# 05_-_Gate_Drivers.net
KiCad netlist of a schematic drawn in Altium Designer
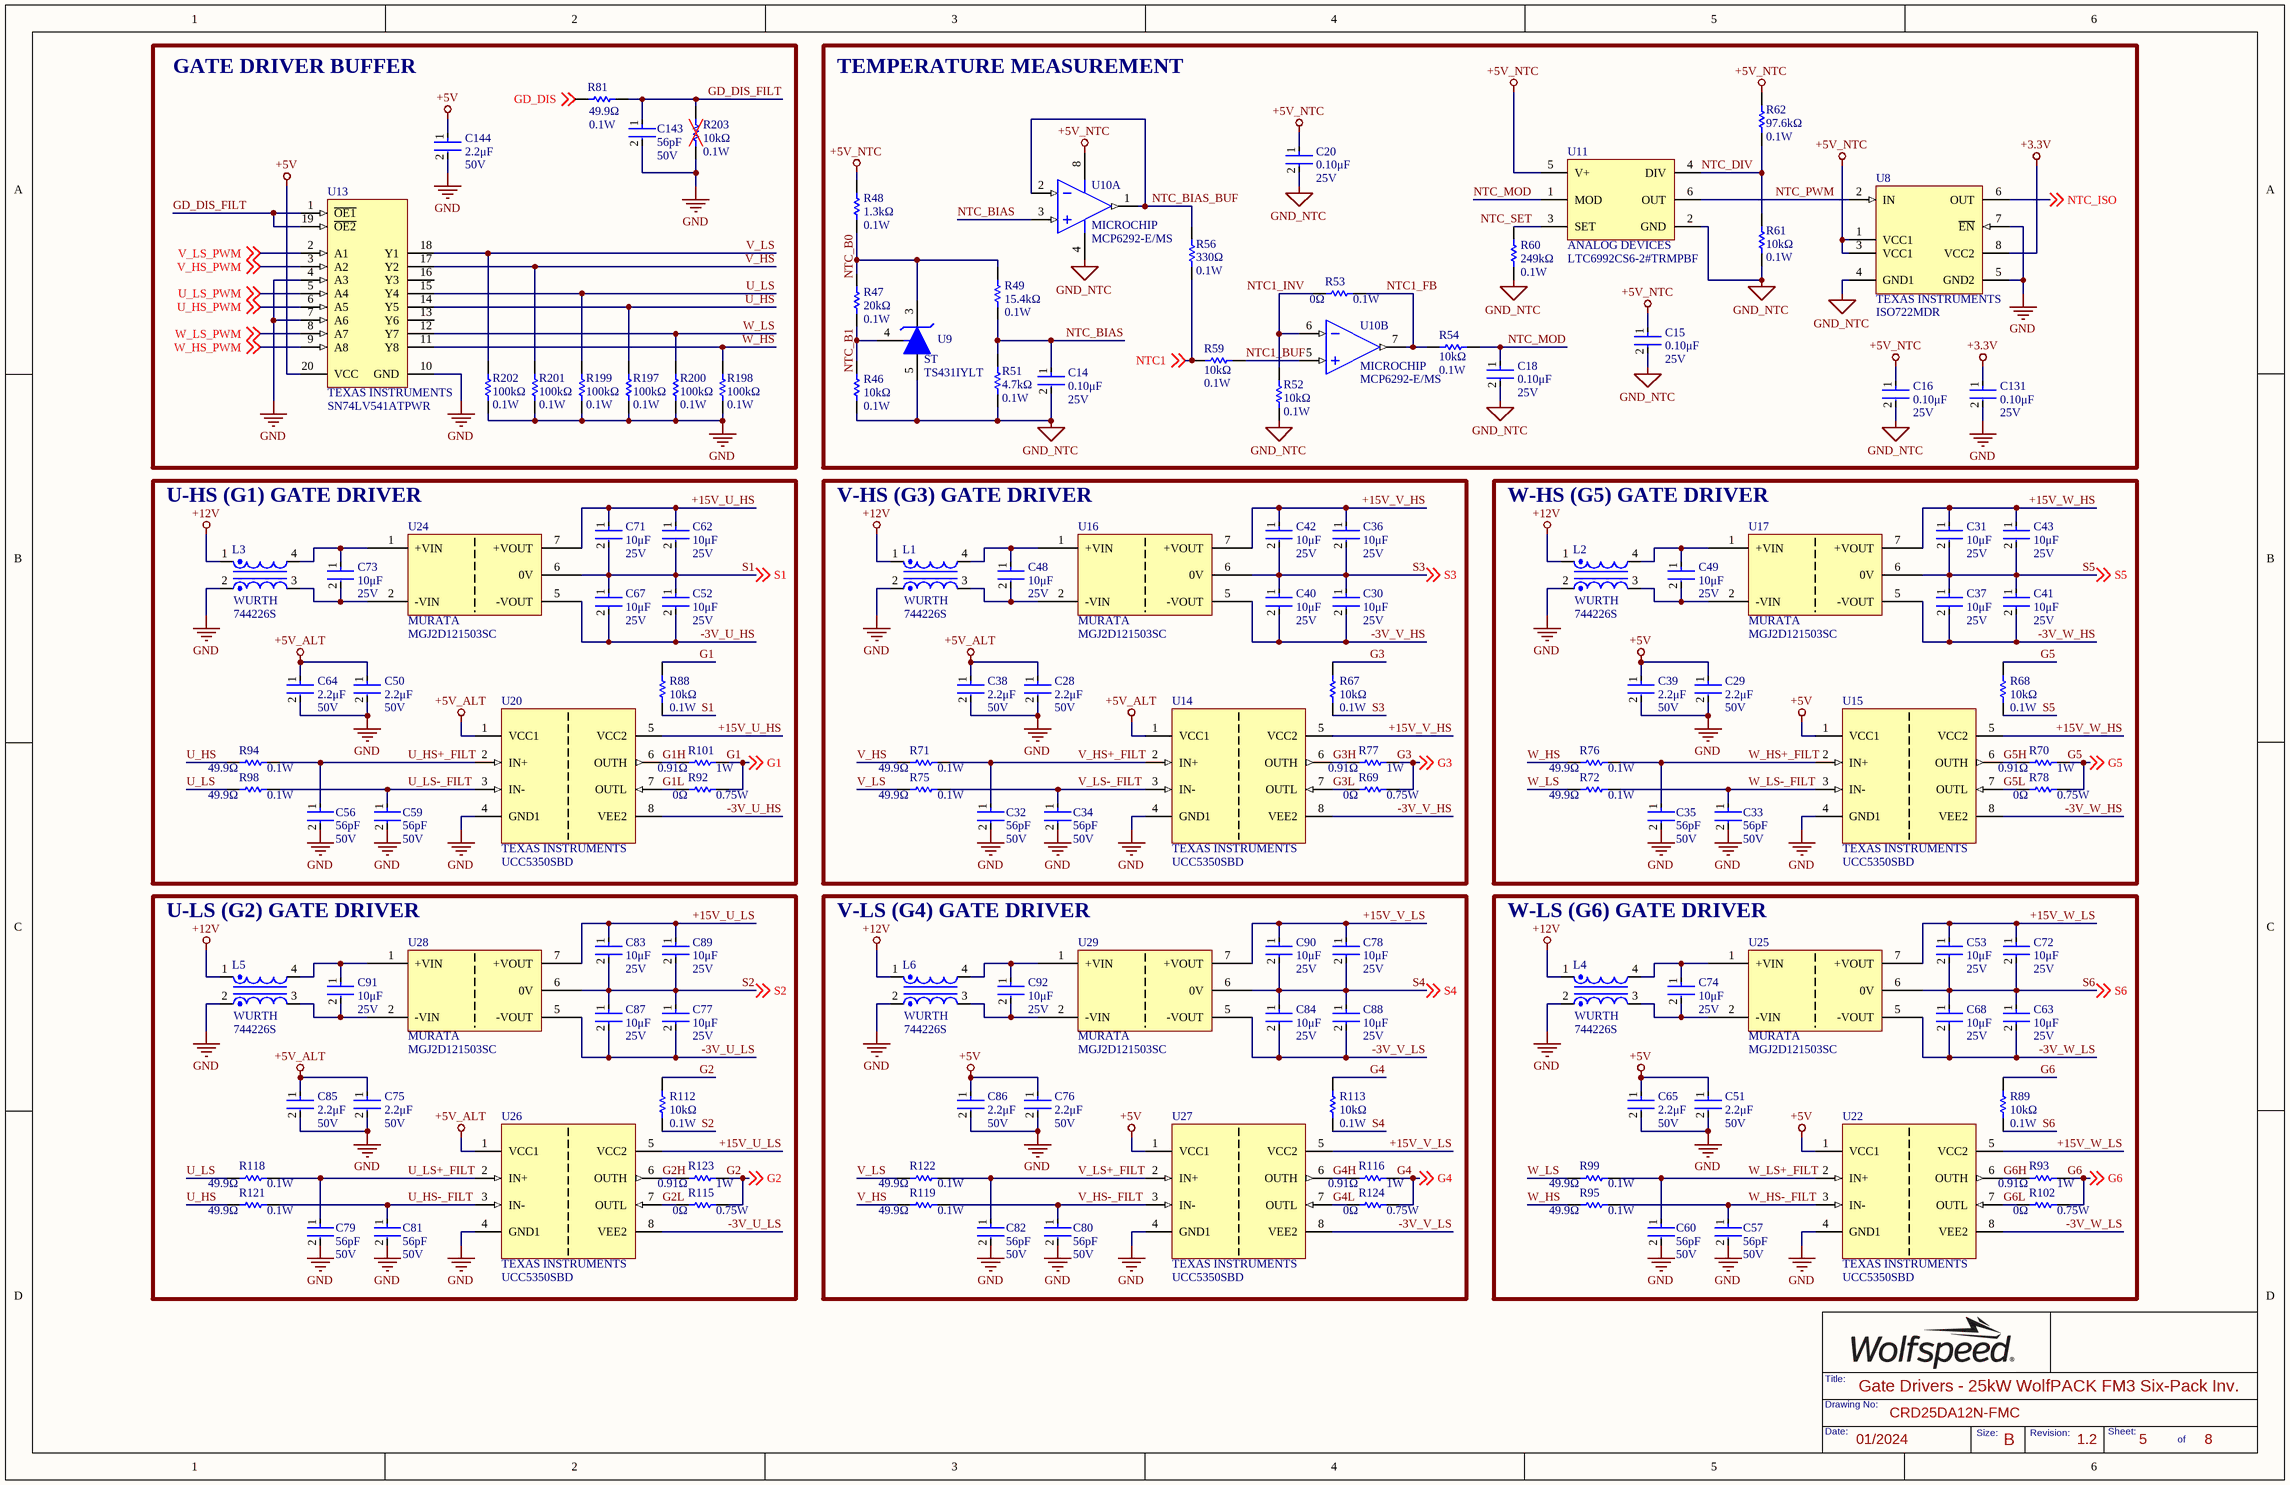
[diagram p0: 05 - Gate Drivers.SchDoc]

(export (version "E")
  (design (tool "Eeschema 10.0.6"))
  (components
    (comp (ref "C14")
      (value "C0603C104K3RACTU")
      (footprint "FP-C0603C-CF-IPC_B")
      (description "CAP CER 0.1UF 25V X7R 0603")
      (fields
        (field (name "VOLTAGE RATING") "25V")
        (field (name "OCTOPART") "https://octopart.com/c0603c104k3ractu-kemet-127541")
        (field (name "MANUFACTURER") "KEMET")
        (field (name "CAPACITANCE") "0.10μF")
      )
      (libsource (lib "Altium Content Vault") (part "b4654b650e69147ec39a6b967a45e02"))
    )
    (comp (ref "C15")
      (value "C0603C104K3RACTU")
      (footprint "FP-C0603C-CF-IPC_B")
      (description "CAP CER 0.1UF 25V X7R 0603")
      (fields
        (field (name "VOLTAGE RATING") "25V")
        (field (name "OCTOPART") "https://octopart.com/c0603c104k3ractu-kemet-127541")
        (field (name "MANUFACTURER") "KEMET")
        (field (name "CAPACITANCE") "0.10μF")
      )
      (libsource (lib "Altium Content Vault") (part "b4654b650e69147ec39a6b967a45e02"))
    )
    (comp (ref "C16")
      (value "C0603C104K3RACTU")
      (footprint "FP-C0603C-CF-IPC_B")
      (description "CAP CER 0.1UF 25V X7R 0603")
      (fields
        (field (name "VOLTAGE RATING") "25V")
        (field (name "OCTOPART") "https://octopart.com/c0603c104k3ractu-kemet-127541")
        (field (name "MANUFACTURER") "KEMET")
        (field (name "CAPACITANCE") "0.10μF")
      )
      (libsource (lib "Altium Content Vault") (part "b4654b650e69147ec39a6b967a45e02"))
    )
    (comp (ref "C18")
      (value "C0603C104K3RACTU")
      (footprint "FP-C0603C-CF-IPC_B")
      (description "CAP CER 0.1UF 25V X7R 0603")
      (fields
        (field (name "VOLTAGE RATING") "25V")
        (field (name "OCTOPART") "https://octopart.com/c0603c104k3ractu-kemet-127541")
        (field (name "MANUFACTURER") "KEMET")
        (field (name "CAPACITANCE") "0.10μF")
      )
      (libsource (lib "Altium Content Vault") (part "b4654b650e69147ec39a6b967a45e02"))
    )
    (comp (ref "C20")
      (value "C0603C104K3RACTU")
      (footprint "FP-C0603C-CF-IPC_B")
      (description "CAP CER 0.1UF 25V X7R 0603")
      (fields
        (field (name "VOLTAGE RATING") "25V")
        (field (name "OCTOPART") "https://octopart.com/c0603c104k3ractu-kemet-127541")
        (field (name "MANUFACTURER") "KEMET")
        (field (name "CAPACITANCE") "0.10μF")
      )
      (libsource (lib "Altium Content Vault") (part "b4654b650e69147ec39a6b967a45e02"))
    )
    (comp (ref "C28")
      (value "GRT188R61H225ME13D")
      (footprint "FP-C0603C-CF-IPC_B")
      (description "CAP CER 2.2UF 50V X5R 0603")
      (fields
        (field (name "MANUFACTURER") "MURATA")
        (field (name "TOLERANCE") "20%")
        (field (name "VOLTAGE RATING") "50V")
        (field (name "CAPACITANCE") "2.2μF")
      )
      (libsource (lib "Inverter_25kW") (part "GRT188R61H225ME13D"))
    )
    (comp (ref "C29")
      (value "GRT188R61H225ME13D")
      (footprint "FP-C0603C-CF-IPC_B")
      (description "CAP CER 2.2UF 50V X5R 0603")
      (fields
        (field (name "MANUFACTURER") "MURATA")
        (field (name "TOLERANCE") "20%")
        (field (name "VOLTAGE RATING") "50V")
        (field (name "CAPACITANCE") "2.2μF")
      )
      (libsource (lib "Inverter_25kW") (part "GRT188R61H225ME13D"))
    )
    (comp (ref "C30")
      (value "CL31B106KAHSFNE")
      (footprint "FP-CL31-IPC_B")
      (description "CAP CER 10UF 25V X7R 1206")
      (fields
        (field (name "VOLTAGE RATING") "25V")
        (field (name "TOLERANCE") "10%")
        (field (name "CAPACITANCE") "10μF")
        (field (name "MANUFACTURER") "SAMSUNG")
      )
      (libsource (lib "Altium Content Vault") (part "b4654b650e69147ec39a6b967a45e02"))
    )
    (comp (ref "C31")
      (value "CL31B106KAHSFNE")
      (footprint "FP-CL31-IPC_B")
      (description "CAP CER 10UF 25V X7R 1206")
      (fields
        (field (name "VOLTAGE RATING") "25V")
        (field (name "TOLERANCE") "10%")
        (field (name "CAPACITANCE") "10μF")
        (field (name "MANUFACTURER") "SAMSUNG")
      )
      (libsource (lib "Altium Content Vault") (part "b4654b650e69147ec39a6b967a45e02"))
    )
    (comp (ref "C32")
      (value "CL10C560JB8NNNC")
      (footprint "FP-C0603C-CF-IPC_B")
      (description "CAP CER 56PF 50V C0G/NP0 0603")
      (fields
        (field (name "MANUFACTURER") "SAMSUNG")
        (field (name "TOLERANCE") "5%")
        (field (name "CAPACITANCE") "56pF")
        (field (name "VOLTAGE RATING") "50V")
      )
      (libsource (lib "Inverter_25kW") (part "CL10C560JB8NNNC"))
    )
    (comp (ref "C33")
      (value "CL10C560JB8NNNC")
      (footprint "FP-C0603C-CF-IPC_B")
      (description "CAP CER 56PF 50V C0G/NP0 0603")
      (fields
        (field (name "MANUFACTURER") "SAMSUNG")
        (field (name "TOLERANCE") "5%")
        (field (name "CAPACITANCE") "56pF")
        (field (name "VOLTAGE RATING") "50V")
      )
      (libsource (lib "Inverter_25kW") (part "CL10C560JB8NNNC"))
    )
    (comp (ref "C34")
      (value "CL10C560JB8NNNC")
      (footprint "FP-C0603C-CF-IPC_B")
      (description "CAP CER 56PF 50V C0G/NP0 0603")
      (fields
        (field (name "MANUFACTURER") "SAMSUNG")
        (field (name "TOLERANCE") "5%")
        (field (name "CAPACITANCE") "56pF")
        (field (name "VOLTAGE RATING") "50V")
      )
      (libsource (lib "Inverter_25kW") (part "CL10C560JB8NNNC"))
    )
    (comp (ref "C35")
      (value "CL10C560JB8NNNC")
      (footprint "FP-C0603C-CF-IPC_B")
      (description "CAP CER 56PF 50V C0G/NP0 0603")
      (fields
        (field (name "MANUFACTURER") "SAMSUNG")
        (field (name "TOLERANCE") "5%")
        (field (name "CAPACITANCE") "56pF")
        (field (name "VOLTAGE RATING") "50V")
      )
      (libsource (lib "Inverter_25kW") (part "CL10C560JB8NNNC"))
    )
    (comp (ref "C36")
      (value "CL31B106KAHSFNE")
      (footprint "FP-CL31-IPC_B")
      (description "CAP CER 10UF 25V X7R 1206")
      (fields
        (field (name "VOLTAGE RATING") "25V")
        (field (name "TOLERANCE") "10%")
        (field (name "CAPACITANCE") "10μF")
        (field (name "MANUFACTURER") "SAMSUNG")
      )
      (libsource (lib "Altium Content Vault") (part "b4654b650e69147ec39a6b967a45e02"))
    )
    (comp (ref "C37")
      (value "CL31B106KAHSFNE")
      (footprint "FP-CL31-IPC_B")
      (description "CAP CER 10UF 25V X7R 1206")
      (fields
        (field (name "VOLTAGE RATING") "25V")
        (field (name "TOLERANCE") "10%")
        (field (name "CAPACITANCE") "10μF")
        (field (name "MANUFACTURER") "SAMSUNG")
      )
      (libsource (lib "Altium Content Vault") (part "b4654b650e69147ec39a6b967a45e02"))
    )
    (comp (ref "C38")
      (value "GRT188R61H225ME13D")
      (footprint "FP-C0603C-CF-IPC_B")
      (description "CAP CER 2.2UF 50V X5R 0603")
      (fields
        (field (name "MANUFACTURER") "MURATA")
        (field (name "TOLERANCE") "20%")
        (field (name "VOLTAGE RATING") "50V")
        (field (name "CAPACITANCE") "2.2μF")
      )
      (libsource (lib "Inverter_25kW") (part "GRT188R61H225ME13D"))
    )
    (comp (ref "C39")
      (value "GRT188R61H225ME13D")
      (footprint "FP-C0603C-CF-IPC_B")
      (description "CAP CER 2.2UF 50V X5R 0603")
      (fields
        (field (name "MANUFACTURER") "MURATA")
        (field (name "TOLERANCE") "20%")
        (field (name "VOLTAGE RATING") "50V")
        (field (name "CAPACITANCE") "2.2μF")
      )
      (libsource (lib "Inverter_25kW") (part "GRT188R61H225ME13D"))
    )
    (comp (ref "C40")
      (value "CL31B106KAHSFNE")
      (footprint "FP-CL31-IPC_B")
      (description "CAP CER 10UF 25V X7R 1206")
      (fields
        (field (name "VOLTAGE RATING") "25V")
        (field (name "TOLERANCE") "10%")
        (field (name "CAPACITANCE") "10μF")
        (field (name "MANUFACTURER") "SAMSUNG")
      )
      (libsource (lib "Altium Content Vault") (part "b4654b650e69147ec39a6b967a45e02"))
    )
    (comp (ref "C41")
      (value "CL31B106KAHSFNE")
      (footprint "FP-CL31-IPC_B")
      (description "CAP CER 10UF 25V X7R 1206")
      (fields
        (field (name "VOLTAGE RATING") "25V")
        (field (name "TOLERANCE") "10%")
        (field (name "CAPACITANCE") "10μF")
        (field (name "MANUFACTURER") "SAMSUNG")
      )
      (libsource (lib "Altium Content Vault") (part "b4654b650e69147ec39a6b967a45e02"))
    )
    (comp (ref "C42")
      (value "CL31B106KAHSFNE")
      (footprint "FP-CL31-IPC_B")
      (description "CAP CER 10UF 25V X7R 1206")
      (fields
        (field (name "VOLTAGE RATING") "25V")
        (field (name "TOLERANCE") "10%")
        (field (name "CAPACITANCE") "10μF")
        (field (name "MANUFACTURER") "SAMSUNG")
      )
      (libsource (lib "Altium Content Vault") (part "b4654b650e69147ec39a6b967a45e02"))
    )
    (comp (ref "C43")
      (value "CL31B106KAHSFNE")
      (footprint "FP-CL31-IPC_B")
      (description "CAP CER 10UF 25V X7R 1206")
      (fields
        (field (name "VOLTAGE RATING") "25V")
        (field (name "TOLERANCE") "10%")
        (field (name "CAPACITANCE") "10μF")
        (field (name "MANUFACTURER") "SAMSUNG")
      )
      (libsource (lib "Altium Content Vault") (part "b4654b650e69147ec39a6b967a45e02"))
    )
    (comp (ref "C48")
      (value "CL31B106KAHSFNE")
      (footprint "FP-CL31-IPC_B")
      (description "CAP CER 10UF 25V X7R 1206")
      (fields
        (field (name "VOLTAGE RATING") "25V")
        (field (name "TOLERANCE") "10%")
        (field (name "CAPACITANCE") "10μF")
        (field (name "MANUFACTURER") "SAMSUNG")
      )
      (libsource (lib "Altium Content Vault") (part "b4654b650e69147ec39a6b967a45e02"))
    )
    (comp (ref "C49")
      (value "CL31B106KAHSFNE")
      (footprint "FP-CL31-IPC_B")
      (description "CAP CER 10UF 25V X7R 1206")
      (fields
        (field (name "VOLTAGE RATING") "25V")
        (field (name "TOLERANCE") "10%")
        (field (name "CAPACITANCE") "10μF")
        (field (name "MANUFACTURER") "SAMSUNG")
      )
      (libsource (lib "Altium Content Vault") (part "b4654b650e69147ec39a6b967a45e02"))
    )
    (comp (ref "C50")
      (value "GRT188R61H225ME13D")
      (footprint "FP-C0603C-CF-IPC_B")
      (description "CAP CER 2.2UF 50V X5R 0603")
      (fields
        (field (name "MANUFACTURER") "MURATA")
        (field (name "TOLERANCE") "20%")
        (field (name "VOLTAGE RATING") "50V")
        (field (name "CAPACITANCE") "2.2μF")
      )
      (libsource (lib "Inverter_25kW") (part "GRT188R61H225ME13D"))
    )
    (comp (ref "C51")
      (value "GRT188R61H225ME13D")
      (footprint "FP-C0603C-CF-IPC_B")
      (description "CAP CER 2.2UF 50V X5R 0603")
      (fields
        (field (name "MANUFACTURER") "MURATA")
        (field (name "TOLERANCE") "20%")
        (field (name "VOLTAGE RATING") "50V")
        (field (name "CAPACITANCE") "2.2μF")
      )
      (libsource (lib "Inverter_25kW") (part "GRT188R61H225ME13D"))
    )
    (comp (ref "C52")
      (value "CL31B106KAHSFNE")
      (footprint "FP-CL31-IPC_B")
      (description "CAP CER 10UF 25V X7R 1206")
      (fields
        (field (name "VOLTAGE RATING") "25V")
        (field (name "TOLERANCE") "10%")
        (field (name "CAPACITANCE") "10μF")
        (field (name "MANUFACTURER") "SAMSUNG")
      )
      (libsource (lib "Altium Content Vault") (part "b4654b650e69147ec39a6b967a45e02"))
    )
    (comp (ref "C53")
      (value "CL31B106KAHSFNE")
      (footprint "FP-CL31-IPC_B")
      (description "CAP CER 10UF 25V X7R 1206")
      (fields
        (field (name "VOLTAGE RATING") "25V")
        (field (name "TOLERANCE") "10%")
        (field (name "CAPACITANCE") "10μF")
        (field (name "MANUFACTURER") "SAMSUNG")
      )
      (libsource (lib "Altium Content Vault") (part "b4654b650e69147ec39a6b967a45e02"))
    )
    (comp (ref "C56")
      (value "CL10C560JB8NNNC")
      (footprint "FP-C0603C-CF-IPC_B")
      (description "CAP CER 56PF 50V C0G/NP0 0603")
      (fields
        (field (name "MANUFACTURER") "SAMSUNG")
        (field (name "TOLERANCE") "5%")
        (field (name "CAPACITANCE") "56pF")
        (field (name "VOLTAGE RATING") "50V")
      )
      (libsource (lib "Inverter_25kW") (part "CL10C560JB8NNNC"))
    )
    (comp (ref "C57")
      (value "CL10C560JB8NNNC")
      (footprint "FP-C0603C-CF-IPC_B")
      (description "CAP CER 56PF 50V C0G/NP0 0603")
      (fields
        (field (name "MANUFACTURER") "SAMSUNG")
        (field (name "TOLERANCE") "5%")
        (field (name "CAPACITANCE") "56pF")
        (field (name "VOLTAGE RATING") "50V")
      )
      (libsource (lib "Inverter_25kW") (part "CL10C560JB8NNNC"))
    )
    (comp (ref "C59")
      (value "CL10C560JB8NNNC")
      (footprint "FP-C0603C-CF-IPC_B")
      (description "CAP CER 56PF 50V C0G/NP0 0603")
      (fields
        (field (name "MANUFACTURER") "SAMSUNG")
        (field (name "TOLERANCE") "5%")
        (field (name "CAPACITANCE") "56pF")
        (field (name "VOLTAGE RATING") "50V")
      )
      (libsource (lib "Inverter_25kW") (part "CL10C560JB8NNNC"))
    )
    (comp (ref "C60")
      (value "CL10C560JB8NNNC")
      (footprint "FP-C0603C-CF-IPC_B")
      (description "CAP CER 56PF 50V C0G/NP0 0603")
      (fields
        (field (name "MANUFACTURER") "SAMSUNG")
        (field (name "TOLERANCE") "5%")
        (field (name "CAPACITANCE") "56pF")
        (field (name "VOLTAGE RATING") "50V")
      )
      (libsource (lib "Inverter_25kW") (part "CL10C560JB8NNNC"))
    )
    (comp (ref "C62")
      (value "CL31B106KAHSFNE")
      (footprint "FP-CL31-IPC_B")
      (description "CAP CER 10UF 25V X7R 1206")
      (fields
        (field (name "VOLTAGE RATING") "25V")
        (field (name "TOLERANCE") "10%")
        (field (name "CAPACITANCE") "10μF")
        (field (name "MANUFACTURER") "SAMSUNG")
      )
      (libsource (lib "Altium Content Vault") (part "b4654b650e69147ec39a6b967a45e02"))
    )
    (comp (ref "C63")
      (value "CL31B106KAHSFNE")
      (footprint "FP-CL31-IPC_B")
      (description "CAP CER 10UF 25V X7R 1206")
      (fields
        (field (name "VOLTAGE RATING") "25V")
        (field (name "TOLERANCE") "10%")
        (field (name "CAPACITANCE") "10μF")
        (field (name "MANUFACTURER") "SAMSUNG")
      )
      (libsource (lib "Altium Content Vault") (part "b4654b650e69147ec39a6b967a45e02"))
    )
    (comp (ref "C64")
      (value "GRT188R61H225ME13D")
      (footprint "FP-C0603C-CF-IPC_B")
      (description "CAP CER 2.2UF 50V X5R 0603")
      (fields
        (field (name "MANUFACTURER") "MURATA")
        (field (name "TOLERANCE") "20%")
        (field (name "VOLTAGE RATING") "50V")
        (field (name "CAPACITANCE") "2.2μF")
      )
      (libsource (lib "Inverter_25kW") (part "GRT188R61H225ME13D"))
    )
    (comp (ref "C65")
      (value "GRT188R61H225ME13D")
      (footprint "FP-C0603C-CF-IPC_B")
      (description "CAP CER 2.2UF 50V X5R 0603")
      (fields
        (field (name "MANUFACTURER") "MURATA")
        (field (name "TOLERANCE") "20%")
        (field (name "VOLTAGE RATING") "50V")
        (field (name "CAPACITANCE") "2.2μF")
      )
      (libsource (lib "Inverter_25kW") (part "GRT188R61H225ME13D"))
    )
    (comp (ref "C67")
      (value "CL31B106KAHSFNE")
      (footprint "FP-CL31-IPC_B")
      (description "CAP CER 10UF 25V X7R 1206")
      (fields
        (field (name "VOLTAGE RATING") "25V")
        (field (name "TOLERANCE") "10%")
        (field (name "CAPACITANCE") "10μF")
        (field (name "MANUFACTURER") "SAMSUNG")
      )
      (libsource (lib "Altium Content Vault") (part "b4654b650e69147ec39a6b967a45e02"))
    )
    (comp (ref "C68")
      (value "CL31B106KAHSFNE")
      (footprint "FP-CL31-IPC_B")
      (description "CAP CER 10UF 25V X7R 1206")
      (fields
        (field (name "VOLTAGE RATING") "25V")
        (field (name "TOLERANCE") "10%")
        (field (name "CAPACITANCE") "10μF")
        (field (name "MANUFACTURER") "SAMSUNG")
      )
      (libsource (lib "Altium Content Vault") (part "b4654b650e69147ec39a6b967a45e02"))
    )
    (comp (ref "C71")
      (value "CL31B106KAHSFNE")
      (footprint "FP-CL31-IPC_B")
      (description "CAP CER 10UF 25V X7R 1206")
      (fields
        (field (name "VOLTAGE RATING") "25V")
        (field (name "TOLERANCE") "10%")
        (field (name "CAPACITANCE") "10μF")
        (field (name "MANUFACTURER") "SAMSUNG")
      )
      (libsource (lib "Altium Content Vault") (part "b4654b650e69147ec39a6b967a45e02"))
    )
    (comp (ref "C72")
      (value "CL31B106KAHSFNE")
      (footprint "FP-CL31-IPC_B")
      (description "CAP CER 10UF 25V X7R 1206")
      (fields
        (field (name "VOLTAGE RATING") "25V")
        (field (name "TOLERANCE") "10%")
        (field (name "CAPACITANCE") "10μF")
        (field (name "MANUFACTURER") "SAMSUNG")
      )
      (libsource (lib "Altium Content Vault") (part "b4654b650e69147ec39a6b967a45e02"))
    )
    (comp (ref "C73")
      (value "CL31B106KAHSFNE")
      (footprint "FP-CL31-IPC_B")
      (description "CAP CER 10UF 25V X7R 1206")
      (fields
        (field (name "VOLTAGE RATING") "25V")
        (field (name "TOLERANCE") "10%")
        (field (name "CAPACITANCE") "10μF")
        (field (name "MANUFACTURER") "SAMSUNG")
      )
      (libsource (lib "Altium Content Vault") (part "b4654b650e69147ec39a6b967a45e02"))
    )
    (comp (ref "C74")
      (value "CL31B106KAHSFNE")
      (footprint "FP-CL31-IPC_B")
      (description "CAP CER 10UF 25V X7R 1206")
      (fields
        (field (name "VOLTAGE RATING") "25V")
        (field (name "TOLERANCE") "10%")
        (field (name "CAPACITANCE") "10μF")
        (field (name "MANUFACTURER") "SAMSUNG")
      )
      (libsource (lib "Altium Content Vault") (part "b4654b650e69147ec39a6b967a45e02"))
    )
    (comp (ref "C75")
      (value "GRT188R61H225ME13D")
      (footprint "FP-C0603C-CF-IPC_B")
      (description "CAP CER 2.2UF 50V X5R 0603")
      (fields
        (field (name "MANUFACTURER") "MURATA")
        (field (name "TOLERANCE") "20%")
        (field (name "VOLTAGE RATING") "50V")
        (field (name "CAPACITANCE") "2.2μF")
      )
      (libsource (lib "Inverter_25kW") (part "GRT188R61H225ME13D"))
    )
    (comp (ref "C76")
      (value "GRT188R61H225ME13D")
      (footprint "FP-C0603C-CF-IPC_B")
      (description "CAP CER 2.2UF 50V X5R 0603")
      (fields
        (field (name "MANUFACTURER") "MURATA")
        (field (name "TOLERANCE") "20%")
        (field (name "VOLTAGE RATING") "50V")
        (field (name "CAPACITANCE") "2.2μF")
      )
      (libsource (lib "Inverter_25kW") (part "GRT188R61H225ME13D"))
    )
    (comp (ref "C77")
      (value "CL31B106KAHSFNE")
      (footprint "FP-CL31-IPC_B")
      (description "CAP CER 10UF 25V X7R 1206")
      (fields
        (field (name "VOLTAGE RATING") "25V")
        (field (name "TOLERANCE") "10%")
        (field (name "CAPACITANCE") "10μF")
        (field (name "MANUFACTURER") "SAMSUNG")
      )
      (libsource (lib "Altium Content Vault") (part "b4654b650e69147ec39a6b967a45e02"))
    )
    (comp (ref "C78")
      (value "CL31B106KAHSFNE")
      (footprint "FP-CL31-IPC_B")
      (description "CAP CER 10UF 25V X7R 1206")
      (fields
        (field (name "VOLTAGE RATING") "25V")
        (field (name "TOLERANCE") "10%")
        (field (name "CAPACITANCE") "10μF")
        (field (name "MANUFACTURER") "SAMSUNG")
      )
      (libsource (lib "Altium Content Vault") (part "b4654b650e69147ec39a6b967a45e02"))
    )
    (comp (ref "C79")
      (value "CL10C560JB8NNNC")
      (footprint "FP-C0603C-CF-IPC_B")
      (description "CAP CER 56PF 50V C0G/NP0 0603")
      (fields
        (field (name "MANUFACTURER") "SAMSUNG")
        (field (name "TOLERANCE") "5%")
        (field (name "CAPACITANCE") "56pF")
        (field (name "VOLTAGE RATING") "50V")
      )
      (libsource (lib "Inverter_25kW") (part "CL10C560JB8NNNC"))
    )
    (comp (ref "C80")
      (value "CL10C560JB8NNNC")
      (footprint "FP-C0603C-CF-IPC_B")
      (description "CAP CER 56PF 50V C0G/NP0 0603")
      (fields
        (field (name "MANUFACTURER") "SAMSUNG")
        (field (name "TOLERANCE") "5%")
        (field (name "CAPACITANCE") "56pF")
        (field (name "VOLTAGE RATING") "50V")
      )
      (libsource (lib "Inverter_25kW") (part "CL10C560JB8NNNC"))
    )
    (comp (ref "C81")
      (value "CL10C560JB8NNNC")
      (footprint "FP-C0603C-CF-IPC_B")
      (description "CAP CER 56PF 50V C0G/NP0 0603")
      (fields
        (field (name "MANUFACTURER") "SAMSUNG")
        (field (name "TOLERANCE") "5%")
        (field (name "CAPACITANCE") "56pF")
        (field (name "VOLTAGE RATING") "50V")
      )
      (libsource (lib "Inverter_25kW") (part "CL10C560JB8NNNC"))
    )
    (comp (ref "C82")
      (value "CL10C560JB8NNNC")
      (footprint "FP-C0603C-CF-IPC_B")
      (description "CAP CER 56PF 50V C0G/NP0 0603")
      (fields
        (field (name "MANUFACTURER") "SAMSUNG")
        (field (name "TOLERANCE") "5%")
        (field (name "CAPACITANCE") "56pF")
        (field (name "VOLTAGE RATING") "50V")
      )
      (libsource (lib "Inverter_25kW") (part "CL10C560JB8NNNC"))
    )
    (comp (ref "C83")
      (value "CL31B106KAHSFNE")
      (footprint "FP-CL31-IPC_B")
      (description "CAP CER 10UF 25V X7R 1206")
      (fields
        (field (name "VOLTAGE RATING") "25V")
        (field (name "TOLERANCE") "10%")
        (field (name "CAPACITANCE") "10μF")
        (field (name "MANUFACTURER") "SAMSUNG")
      )
      (libsource (lib "Altium Content Vault") (part "b4654b650e69147ec39a6b967a45e02"))
    )
    (comp (ref "C84")
      (value "CL31B106KAHSFNE")
      (footprint "FP-CL31-IPC_B")
      (description "CAP CER 10UF 25V X7R 1206")
      (fields
        (field (name "VOLTAGE RATING") "25V")
        (field (name "TOLERANCE") "10%")
        (field (name "CAPACITANCE") "10μF")
        (field (name "MANUFACTURER") "SAMSUNG")
      )
      (libsource (lib "Altium Content Vault") (part "b4654b650e69147ec39a6b967a45e02"))
    )
    (comp (ref "C85")
      (value "GRT188R61H225ME13D")
      (footprint "FP-C0603C-CF-IPC_B")
      (description "CAP CER 2.2UF 50V X5R 0603")
      (fields
        (field (name "MANUFACTURER") "MURATA")
        (field (name "TOLERANCE") "20%")
        (field (name "VOLTAGE RATING") "50V")
        (field (name "CAPACITANCE") "2.2μF")
      )
      (libsource (lib "Inverter_25kW") (part "GRT188R61H225ME13D"))
    )
    (comp (ref "C86")
      (value "GRT188R61H225ME13D")
      (footprint "FP-C0603C-CF-IPC_B")
      (description "CAP CER 2.2UF 50V X5R 0603")
      (fields
        (field (name "MANUFACTURER") "MURATA")
        (field (name "TOLERANCE") "20%")
        (field (name "VOLTAGE RATING") "50V")
        (field (name "CAPACITANCE") "2.2μF")
      )
      (libsource (lib "Inverter_25kW") (part "GRT188R61H225ME13D"))
    )
    (comp (ref "C87")
      (value "CL31B106KAHSFNE")
      (footprint "FP-CL31-IPC_B")
      (description "CAP CER 10UF 25V X7R 1206")
      (fields
        (field (name "VOLTAGE RATING") "25V")
        (field (name "TOLERANCE") "10%")
        (field (name "CAPACITANCE") "10μF")
        (field (name "MANUFACTURER") "SAMSUNG")
      )
      (libsource (lib "Altium Content Vault") (part "b4654b650e69147ec39a6b967a45e02"))
    )
    (comp (ref "C88")
      (value "CL31B106KAHSFNE")
      (footprint "FP-CL31-IPC_B")
      (description "CAP CER 10UF 25V X7R 1206")
      (fields
        (field (name "VOLTAGE RATING") "25V")
        (field (name "TOLERANCE") "10%")
        (field (name "CAPACITANCE") "10μF")
        (field (name "MANUFACTURER") "SAMSUNG")
      )
      (libsource (lib "Altium Content Vault") (part "b4654b650e69147ec39a6b967a45e02"))
    )
    (comp (ref "C89")
      (value "CL31B106KAHSFNE")
      (footprint "FP-CL31-IPC_B")
      (description "CAP CER 10UF 25V X7R 1206")
      (fields
        (field (name "VOLTAGE RATING") "25V")
        (field (name "TOLERANCE") "10%")
        (field (name "CAPACITANCE") "10μF")
        (field (name "MANUFACTURER") "SAMSUNG")
      )
      (libsource (lib "Altium Content Vault") (part "b4654b650e69147ec39a6b967a45e02"))
    )
    (comp (ref "C90")
      (value "CL31B106KAHSFNE")
      (footprint "FP-CL31-IPC_B")
      (description "CAP CER 10UF 25V X7R 1206")
      (fields
        (field (name "VOLTAGE RATING") "25V")
        (field (name "TOLERANCE") "10%")
        (field (name "CAPACITANCE") "10μF")
        (field (name "MANUFACTURER") "SAMSUNG")
      )
      (libsource (lib "Altium Content Vault") (part "b4654b650e69147ec39a6b967a45e02"))
    )
    (comp (ref "C91")
      (value "CL31B106KAHSFNE")
      (footprint "FP-CL31-IPC_B")
      (description "CAP CER 10UF 25V X7R 1206")
      (fields
        (field (name "VOLTAGE RATING") "25V")
        (field (name "TOLERANCE") "10%")
        (field (name "CAPACITANCE") "10μF")
        (field (name "MANUFACTURER") "SAMSUNG")
      )
      (libsource (lib "Altium Content Vault") (part "b4654b650e69147ec39a6b967a45e02"))
    )
    (comp (ref "C92")
      (value "CL31B106KAHSFNE")
      (footprint "FP-CL31-IPC_B")
      (description "CAP CER 10UF 25V X7R 1206")
      (fields
        (field (name "VOLTAGE RATING") "25V")
        (field (name "TOLERANCE") "10%")
        (field (name "CAPACITANCE") "10μF")
        (field (name "MANUFACTURER") "SAMSUNG")
      )
      (libsource (lib "Altium Content Vault") (part "b4654b650e69147ec39a6b967a45e02"))
    )
    (comp (ref "C131")
      (value "C0603C104K3RACTU")
      (footprint "FP-C0603C-CF-IPC_B")
      (description "CAP CER 0.1UF 25V X7R 0603")
      (fields
        (field (name "VOLTAGE RATING") "25V")
        (field (name "OCTOPART") "https://octopart.com/c0603c104k3ractu-kemet-127541")
        (field (name "MANUFACTURER") "KEMET")
        (field (name "CAPACITANCE") "0.10μF")
      )
      (libsource (lib "Altium Content Vault") (part "b4654b650e69147ec39a6b967a45e02"))
    )
    (comp (ref "C143")
      (value "CL10C560JB8NNNC")
      (footprint "FP-C0603C-CF-IPC_B")
      (description "CAP CER 56PF 50V C0G/NP0 0603")
      (fields
        (field (name "MANUFACTURER") "SAMSUNG")
        (field (name "TOLERANCE") "5%")
        (field (name "CAPACITANCE") "56pF")
        (field (name "VOLTAGE RATING") "50V")
      )
      (libsource (lib "Inverter_25kW") (part "CL10C560JB8NNNC"))
    )
    (comp (ref "C144")
      (value "GRT188R61H225ME13D")
      (footprint "FP-C0603C-CF-IPC_B")
      (description "CAP CER 2.2UF 50V X5R 0603")
      (fields
        (field (name "MANUFACTURER") "MURATA")
        (field (name "TOLERANCE") "20%")
        (field (name "VOLTAGE RATING") "50V")
        (field (name "CAPACITANCE") "2.2μF")
      )
      (libsource (lib "Inverter_25kW") (part "GRT188R61H225ME13D"))
    )
    (comp (ref "L1")
      (value "744226S")
      (footprint "Inverter_25kW:WE-SL2")
      (description "CMC 10UH 1.6A 2LN 920 OHM SMD")
      (fields
        (field (name "MANUFACTURER") "WURTH ELECTRONIK")
        (field (name "TOLERANCE") "30%")
        (field (name "MANUFACTURER PRINT") "WURTH")
      )
      (libsource (lib "Inverter_25kW") (part "744226S"))
    )
    (comp (ref "L2")
      (value "744226S")
      (footprint "Inverter_25kW:WE-SL2")
      (description "CMC 10UH 1.6A 2LN 920 OHM SMD")
      (fields
        (field (name "MANUFACTURER") "WURTH ELECTRONIK")
        (field (name "TOLERANCE") "30%")
        (field (name "MANUFACTURER PRINT") "WURTH")
      )
      (libsource (lib "Inverter_25kW") (part "744226S"))
    )
    (comp (ref "L3")
      (value "744226S")
      (footprint "Inverter_25kW:WE-SL2")
      (description "CMC 10UH 1.6A 2LN 920 OHM SMD")
      (fields
        (field (name "MANUFACTURER") "WURTH ELECTRONIK")
        (field (name "TOLERANCE") "30%")
        (field (name "MANUFACTURER PRINT") "WURTH")
      )
      (libsource (lib "Inverter_25kW") (part "744226S"))
    )
    (comp (ref "L4")
      (value "744226S")
      (footprint "Inverter_25kW:WE-SL2")
      (description "CMC 10UH 1.6A 2LN 920 OHM SMD")
      (fields
        (field (name "MANUFACTURER") "WURTH ELECTRONIK")
        (field (name "TOLERANCE") "30%")
        (field (name "MANUFACTURER PRINT") "WURTH")
      )
      (libsource (lib "Inverter_25kW") (part "744226S"))
    )
    (comp (ref "L5")
      (value "744226S")
      (footprint "Inverter_25kW:WE-SL2")
      (description "CMC 10UH 1.6A 2LN 920 OHM SMD")
      (fields
        (field (name "MANUFACTURER") "WURTH ELECTRONIK")
        (field (name "TOLERANCE") "30%")
        (field (name "MANUFACTURER PRINT") "WURTH")
      )
      (libsource (lib "Inverter_25kW") (part "744226S"))
    )
    (comp (ref "L6")
      (value "744226S")
      (footprint "Inverter_25kW:WE-SL2")
      (description "CMC 10UH 1.6A 2LN 920 OHM SMD")
      (fields
        (field (name "MANUFACTURER") "WURTH ELECTRONIK")
        (field (name "TOLERANCE") "30%")
        (field (name "MANUFACTURER PRINT") "WURTH")
      )
      (libsource (lib "Inverter_25kW") (part "744226S"))
    )
    (comp (ref "R46")
      (value "ERJ3EKF1002V")
      (footprint "FP-MCR03-IPC_B")
      (description "RES SMD 10K OHM 1% 1/10W 0603")
      (fields
        (field (name "MANUFACTURER") "PANASONIC")
        (field (name "MANUFACTURER PART NUMBER") "ERJ-3EKF1002V")
        (field (name "RESISTANCE") "10kΩ")
        (field (name "MAX POWER DISSIPATION") "0.1W")
      )
      (libsource (lib "Inverter_25kW") (part "ERJ3EKF1002V"))
    )
    (comp (ref "R47")
      (value "CRCW060320K0FKTA")
      (footprint "FP-MCR03-IPC_B")
      (description "RES SMD 20K OHM 1% 1/10W 0603")
      (fields
        (field (name "MANUFACTURER") "VISHAY DALE")
        (field (name "TOLERANCE") "1%")
        (field (name "RESISTANCE") "20kΩ")
        (field (name "POWER RATING") "0.1W")
      )
      (libsource (lib "Inverter_25kW") (part "CRCW060320K0FKTA"))
    )
    (comp (ref "R48")
      (value "ERA3AEB132V")
      (footprint "FP-MCR03-IPC_B")
      (description "RES SMD 1.3K OHM 0.1% 1/10W 0603")
      (fields
        (field (name "MANUFACTURER") "PANASONIC")
        (field (name "MANUFACTURER PART NUMBER") "ERA-3AEB132V")
        (field (name "POWER RATING") "0.1W")
        (field (name "RESISTANCE") "1.3kΩ")
      )
      (libsource (lib "Inverter_25kW") (part "ERA3AEB132V"))
    )
    (comp (ref "R49")
      (value "RC1608F1542CS")
      (footprint "FP-MCR03-IPC_B")
      (description "RES SMD 15.4K OHM 1% 1/10W 0603")
      (fields
        (field (name "MANUFACTURER") "SAMSUNG")
        (field (name "TOLERANCE") "1%")
        (field (name "POWER RATING") "0.1W")
        (field (name "RESISTANCE") "15.4kΩ")
      )
      (libsource (lib "Inverter_25kW") (part "RC1608F1542CS"))
    )
    (comp (ref "R51")
      (value "CRCW06034K70FKTA")
      (footprint "FP-MCR03-IPC_B")
      (description "RES SMD 4.7K OHM 1% 1/10W 0603")
      (fields
        (field (name "MANUFACTURER") "VISHAY DALE")
        (field (name "TOLERANCE") "1%")
        (field (name "RESISTANCE") "4.7kΩ")
        (field (name "POWER RATING") "0.1W")
      )
      (libsource (lib "Inverter_25kW") (part "CRCW06034K70FKTA"))
    )
    (comp (ref "R52")
      (value "ERJ3EKF1002V")
      (footprint "FP-MCR03-IPC_B")
      (description "RES SMD 10K OHM 1% 1/10W 0603")
      (fields
        (field (name "MANUFACTURER") "PANASONIC")
        (field (name "MANUFACTURER PART NUMBER") "ERJ-3EKF1002V")
        (field (name "RESISTANCE") "10kΩ")
        (field (name "MAX POWER DISSIPATION") "0.1W")
      )
      (libsource (lib "Inverter_25kW") (part "ERJ3EKF1002V"))
    )
    (comp (ref "R53")
      (value "CRCW06030000Z0EB")
      (footprint "FP-MCR03-IPC_B")
      (description "RES SMD 0 OHM JUMPER 1/10W 0603")
      (fields
        (field (name "MANUFACTURER") "VISHAY DALE")
        (field (name "MANUFACTURER PART NUMBER") "CRCW06030000Z0EBC")
        (field (name "RESISTANCE") "0Ω")
        (field (name "POWER RATING") "0.1W")
      )
      (libsource (lib "Inverter_25kW") (part "CRCW06030000Z0EB"))
    )
    (comp (ref "R54")
      (value "ERJ3EKF1002V")
      (footprint "FP-MCR03-IPC_B")
      (description "RES SMD 10K OHM 1% 1/10W 0603")
      (fields
        (field (name "MANUFACTURER") "PANASONIC")
        (field (name "MANUFACTURER PART NUMBER") "ERJ-3EKF1002V")
        (field (name "RESISTANCE") "10kΩ")
        (field (name "MAX POWER DISSIPATION") "0.1W")
      )
      (libsource (lib "Inverter_25kW") (part "ERJ3EKF1002V"))
    )
    (comp (ref "R56")
      (value "RC0603FR-13330RL")
      (footprint "FP-MCR03-IPC_B")
      (description "RES 330 OHM 1% 1/10W 0603")
      (fields
        (field (name "MANUFACTURER") "YAGEO")
        (field (name "TOLERANCE") "1%")
        (field (name "RESISTANCE") "330Ω")
        (field (name "POWER RATING") "0.1W")
      )
      (libsource (lib "Inverter_25kW") (part "RC0603FR-13330RL"))
    )
    (comp (ref "R59")
      (value "ERJ3EKF1002V")
      (footprint "FP-MCR03-IPC_B")
      (description "RES SMD 10K OHM 1% 1/10W 0603")
      (fields
        (field (name "MANUFACTURER") "PANASONIC")
        (field (name "MANUFACTURER PART NUMBER") "ERJ-3EKF1002V")
        (field (name "RESISTANCE") "10kΩ")
        (field (name "MAX POWER DISSIPATION") "0.1W")
      )
      (libsource (lib "Inverter_25kW") (part "ERJ3EKF1002V"))
    )
    (comp (ref "R60")
      (value "RMCF0603FT249K")
      (footprint "FP-MCR03-IPC_B")
      (description "RES 249K OHM 1% 1/10W 0603")
      (fields
        (field (name "MANUFACTURER") "STACKPOLE")
        (field (name "TOLERANCE") "1%")
        (field (name "MAX POWER DISSIPATION") "0.1W")
        (field (name "RESISTANCE") "249kΩ")
      )
      (libsource (lib "Inverter_25kW") (part "RMCF0603FT249K"))
    )
    (comp (ref "R61")
      (value "ERJ3EKF1002V")
      (footprint "FP-MCR03-IPC_B")
      (description "RES SMD 10K OHM 1% 1/10W 0603")
      (fields
        (field (name "MANUFACTURER") "PANASONIC")
        (field (name "MANUFACTURER PART NUMBER") "ERJ-3EKF1002V")
        (field (name "RESISTANCE") "10kΩ")
        (field (name "MAX POWER DISSIPATION") "0.1W")
      )
      (libsource (lib "Inverter_25kW") (part "ERJ3EKF1002V"))
    )
    (comp (ref "R62")
      (value "ERJ-3EKF9762V")
      (footprint "FP-MCR03-IPC_B")
      (description "RES SMD 97.6K OHM 1% 1/10W 0603")
      (fields
        (field (name "MANUFACTURER") "PANASONIC")
        (field (name "TOLERANCE") "1%")
        (field (name "RESISTANCE") "97.6kΩ")
        (field (name "MAX POWER DISSIPATION") "0.1W")
      )
      (libsource (lib "Inverter_25kW") (part "ERJ-3EKF9762V"))
    )
    (comp (ref "R67")
      (value "ERJ3EKF1002V")
      (footprint "FP-MCR03-IPC_B")
      (description "RES SMD 10K OHM 1% 1/10W 0603")
      (fields
        (field (name "MANUFACTURER") "PANASONIC")
        (field (name "MANUFACTURER PART NUMBER") "ERJ-3EKF1002V")
        (field (name "RESISTANCE") "10kΩ")
        (field (name "MAX POWER DISSIPATION") "0.1W")
      )
      (libsource (lib "Inverter_25kW") (part "ERJ3EKF1002V"))
    )
    (comp (ref "R68")
      (value "ERJ3EKF1002V")
      (footprint "FP-MCR03-IPC_B")
      (description "RES SMD 10K OHM 1% 1/10W 0603")
      (fields
        (field (name "MANUFACTURER") "PANASONIC")
        (field (name "MANUFACTURER PART NUMBER") "ERJ-3EKF1002V")
        (field (name "RESISTANCE") "10kΩ")
        (field (name "MAX POWER DISSIPATION") "0.1W")
      )
      (libsource (lib "Inverter_25kW") (part "ERJ3EKF1002V"))
    )
    (comp (ref "R69")
      (value "0Ω")
      (footprint "RESC3125X70X40NL20T20")
      (description "RES SMD 0 OHM JUMPER 3/4W 1210")
      (fields
        (field (name "MANUFACTURER") "VISHAY DALE")
        (field (name "MANUFACTURER PART NUMBER") "CRCW12100000Z0EAHP")
        (field (name "POWER RATING") "0.75W")
      )
      (libsource (lib "CRD25DA12N-FMC") (part "CRCW12100000Z0EAHP"))
    )
    (comp (ref "R70")
      (value "0.91Ω")
      (footprint "RESC3125X70X40NL20T20")
      (description "RES 0.91 OHM 1% 1W 1210")
      (fields
        (field (name "MANUFACTURER") "VISHAY DALE")
        (field (name "PART NUMBER") "RCWE1210R910FKEA")
        (field (name "POWER") "1W")
      )
      (libsource (lib "Altium Content Vault") (part "RES"))
    )
    (comp (ref "R71")
      (value "ERJ-3EKF49R9V")
      (footprint "FP-MCR03-IPC_B")
      (description "RES SMD 49.9 OHM 1% 1/10W 0603")
      (fields
        (field (name "MANUFACTURER") "PANASONIC")
        (field (name "TOLERANCE") "1%")
        (field (name "RESISTANCE") "49.9Ω")
        (field (name "POWER RATING") "0.1W")
      )
      (libsource (lib "Inverter_25kW") (part "ERJ-3EKF49R9V"))
    )
    (comp (ref "R72")
      (value "ERJ-3EKF49R9V")
      (footprint "FP-MCR03-IPC_B")
      (description "RES SMD 49.9 OHM 1% 1/10W 0603")
      (fields
        (field (name "MANUFACTURER") "PANASONIC")
        (field (name "TOLERANCE") "1%")
        (field (name "RESISTANCE") "49.9Ω")
        (field (name "POWER RATING") "0.1W")
      )
      (libsource (lib "Inverter_25kW") (part "ERJ-3EKF49R9V"))
    )
    (comp (ref "R75")
      (value "ERJ-3EKF49R9V")
      (footprint "FP-MCR03-IPC_B")
      (description "RES SMD 49.9 OHM 1% 1/10W 0603")
      (fields
        (field (name "MANUFACTURER") "PANASONIC")
        (field (name "TOLERANCE") "1%")
        (field (name "RESISTANCE") "49.9Ω")
        (field (name "POWER RATING") "0.1W")
      )
      (libsource (lib "Inverter_25kW") (part "ERJ-3EKF49R9V"))
    )
    (comp (ref "R76")
      (value "ERJ-3EKF49R9V")
      (footprint "FP-MCR03-IPC_B")
      (description "RES SMD 49.9 OHM 1% 1/10W 0603")
      (fields
        (field (name "MANUFACTURER") "PANASONIC")
        (field (name "TOLERANCE") "1%")
        (field (name "RESISTANCE") "49.9Ω")
        (field (name "POWER RATING") "0.1W")
      )
      (libsource (lib "Inverter_25kW") (part "ERJ-3EKF49R9V"))
    )
    (comp (ref "R77")
      (value "0.91Ω")
      (footprint "RESC3125X70X40NL20T20")
      (description "RES 0.91 OHM 1% 1W 1210")
      (fields
        (field (name "MANUFACTURER") "VISHAY DALE")
        (field (name "PART NUMBER") "RCWE1210R910FKEA")
        (field (name "POWER") "1W")
      )
      (libsource (lib "Altium Content Vault") (part "RES"))
    )
    (comp (ref "R78")
      (value "0Ω")
      (footprint "RESC3125X70X40NL20T20")
      (description "RES SMD 0 OHM JUMPER 3/4W 1210")
      (fields
        (field (name "MANUFACTURER") "VISHAY DALE")
        (field (name "MANUFACTURER PART NUMBER") "CRCW12100000Z0EAHP")
        (field (name "POWER RATING") "0.75W")
      )
      (libsource (lib "CRD25DA12N-FMC") (part "CRCW12100000Z0EAHP"))
    )
    (comp (ref "R81")
      (value "ERJ-3EKF49R9V")
      (footprint "FP-MCR03-IPC_B")
      (description "RES SMD 49.9 OHM 1% 1/10W 0603")
      (fields
        (field (name "MANUFACTURER") "PANASONIC")
        (field (name "TOLERANCE") "1%")
        (field (name "RESISTANCE") "49.9Ω")
        (field (name "POWER RATING") "0.1W")
      )
      (libsource (lib "Inverter_25kW") (part "ERJ-3EKF49R9V"))
    )
    (comp (ref "R88")
      (value "ERJ3EKF1002V")
      (footprint "FP-MCR03-IPC_B")
      (description "RES SMD 10K OHM 1% 1/10W 0603")
      (fields
        (field (name "MANUFACTURER") "PANASONIC")
        (field (name "MANUFACTURER PART NUMBER") "ERJ-3EKF1002V")
        (field (name "RESISTANCE") "10kΩ")
        (field (name "MAX POWER DISSIPATION") "0.1W")
      )
      (libsource (lib "Inverter_25kW") (part "ERJ3EKF1002V"))
    )
    (comp (ref "R89")
      (value "ERJ3EKF1002V")
      (footprint "FP-MCR03-IPC_B")
      (description "RES SMD 10K OHM 1% 1/10W 0603")
      (fields
        (field (name "MANUFACTURER") "PANASONIC")
        (field (name "MANUFACTURER PART NUMBER") "ERJ-3EKF1002V")
        (field (name "RESISTANCE") "10kΩ")
        (field (name "MAX POWER DISSIPATION") "0.1W")
      )
      (libsource (lib "Inverter_25kW") (part "ERJ3EKF1002V"))
    )
    (comp (ref "R92")
      (value "0Ω")
      (footprint "RESC3125X70X40NL20T20")
      (description "RES SMD 0 OHM JUMPER 3/4W 1210")
      (fields
        (field (name "MANUFACTURER") "VISHAY DALE")
        (field (name "MANUFACTURER PART NUMBER") "CRCW12100000Z0EAHP")
        (field (name "POWER RATING") "0.75W")
      )
      (libsource (lib "CRD25DA12N-FMC") (part "CRCW12100000Z0EAHP"))
    )
    (comp (ref "R93")
      (value "0.91Ω")
      (footprint "RESC3125X70X40NL20T20")
      (description "RES 0.91 OHM 1% 1W 1210")
      (fields
        (field (name "MANUFACTURER") "VISHAY DALE")
        (field (name "PART NUMBER") "RCWE1210R910FKEA")
        (field (name "POWER") "1W")
      )
      (libsource (lib "Altium Content Vault") (part "RES"))
    )
    (comp (ref "R94")
      (value "ERJ-3EKF49R9V")
      (footprint "FP-MCR03-IPC_B")
      (description "RES SMD 49.9 OHM 1% 1/10W 0603")
      (fields
        (field (name "MANUFACTURER") "PANASONIC")
        (field (name "TOLERANCE") "1%")
        (field (name "RESISTANCE") "49.9Ω")
        (field (name "POWER RATING") "0.1W")
      )
      (libsource (lib "Inverter_25kW") (part "ERJ-3EKF49R9V"))
    )
    (comp (ref "R95")
      (value "ERJ-3EKF49R9V")
      (footprint "FP-MCR03-IPC_B")
      (description "RES SMD 49.9 OHM 1% 1/10W 0603")
      (fields
        (field (name "MANUFACTURER") "PANASONIC")
        (field (name "TOLERANCE") "1%")
        (field (name "RESISTANCE") "49.9Ω")
        (field (name "POWER RATING") "0.1W")
      )
      (libsource (lib "Inverter_25kW") (part "ERJ-3EKF49R9V"))
    )
    (comp (ref "R98")
      (value "ERJ-3EKF49R9V")
      (footprint "FP-MCR03-IPC_B")
      (description "RES SMD 49.9 OHM 1% 1/10W 0603")
      (fields
        (field (name "MANUFACTURER") "PANASONIC")
        (field (name "TOLERANCE") "1%")
        (field (name "RESISTANCE") "49.9Ω")
        (field (name "POWER RATING") "0.1W")
      )
      (libsource (lib "Inverter_25kW") (part "ERJ-3EKF49R9V"))
    )
    (comp (ref "R99")
      (value "ERJ-3EKF49R9V")
      (footprint "FP-MCR03-IPC_B")
      (description "RES SMD 49.9 OHM 1% 1/10W 0603")
      (fields
        (field (name "MANUFACTURER") "PANASONIC")
        (field (name "TOLERANCE") "1%")
        (field (name "RESISTANCE") "49.9Ω")
        (field (name "POWER RATING") "0.1W")
      )
      (libsource (lib "Inverter_25kW") (part "ERJ-3EKF49R9V"))
    )
    (comp (ref "R101")
      (value "0.91Ω")
      (footprint "RESC3125X70X40NL20T20")
      (description "RES 0.91 OHM 1% 1W 1210")
      (fields
        (field (name "MANUFACTURER") "VISHAY DALE")
        (field (name "PART NUMBER") "RCWE1210R910FKEA")
        (field (name "POWER") "1W")
      )
      (libsource (lib "Altium Content Vault") (part "RES"))
    )
    (comp (ref "R102")
      (value "0Ω")
      (footprint "RESC3125X70X40NL20T20")
      (description "RES SMD 0 OHM JUMPER 3/4W 1210")
      (fields
        (field (name "MANUFACTURER") "VISHAY DALE")
        (field (name "MANUFACTURER PART NUMBER") "CRCW12100000Z0EAHP")
        (field (name "POWER RATING") "0.75W")
      )
      (libsource (lib "CRD25DA12N-FMC") (part "CRCW12100000Z0EAHP"))
    )
    (comp (ref "R112")
      (value "ERJ3EKF1002V")
      (footprint "FP-MCR03-IPC_B")
      (description "RES SMD 10K OHM 1% 1/10W 0603")
      (fields
        (field (name "MANUFACTURER") "PANASONIC")
        (field (name "MANUFACTURER PART NUMBER") "ERJ-3EKF1002V")
        (field (name "RESISTANCE") "10kΩ")
        (field (name "MAX POWER DISSIPATION") "0.1W")
      )
      (libsource (lib "Inverter_25kW") (part "ERJ3EKF1002V"))
    )
    (comp (ref "R113")
      (value "ERJ3EKF1002V")
      (footprint "FP-MCR03-IPC_B")
      (description "RES SMD 10K OHM 1% 1/10W 0603")
      (fields
        (field (name "MANUFACTURER") "PANASONIC")
        (field (name "MANUFACTURER PART NUMBER") "ERJ-3EKF1002V")
        (field (name "RESISTANCE") "10kΩ")
        (field (name "MAX POWER DISSIPATION") "0.1W")
      )
      (libsource (lib "Inverter_25kW") (part "ERJ3EKF1002V"))
    )
    (comp (ref "R115")
      (value "0Ω")
      (footprint "RESC3125X70X40NL20T20")
      (description "RES SMD 0 OHM JUMPER 3/4W 1210")
      (fields
        (field (name "MANUFACTURER") "VISHAY DALE")
        (field (name "MANUFACTURER PART NUMBER") "CRCW12100000Z0EAHP")
        (field (name "POWER RATING") "0.75W")
      )
      (libsource (lib "CRD25DA12N-FMC") (part "CRCW12100000Z0EAHP"))
    )
    (comp (ref "R116")
      (value "0.91Ω")
      (footprint "RESC3125X70X40NL20T20")
      (description "RES 0.91 OHM 1% 1W 1210")
      (fields
        (field (name "MANUFACTURER") "VISHAY DALE")
        (field (name "PART NUMBER") "RCWE1210R910FKEA")
        (field (name "POWER") "1W")
      )
      (libsource (lib "Altium Content Vault") (part "RES"))
    )
    (comp (ref "R118")
      (value "ERJ-3EKF49R9V")
      (footprint "FP-MCR03-IPC_B")
      (description "RES SMD 49.9 OHM 1% 1/10W 0603")
      (fields
        (field (name "MANUFACTURER") "PANASONIC")
        (field (name "TOLERANCE") "1%")
        (field (name "RESISTANCE") "49.9Ω")
        (field (name "POWER RATING") "0.1W")
      )
      (libsource (lib "Inverter_25kW") (part "ERJ-3EKF49R9V"))
    )
    (comp (ref "R119")
      (value "ERJ-3EKF49R9V")
      (footprint "FP-MCR03-IPC_B")
      (description "RES SMD 49.9 OHM 1% 1/10W 0603")
      (fields
        (field (name "MANUFACTURER") "PANASONIC")
        (field (name "TOLERANCE") "1%")
        (field (name "RESISTANCE") "49.9Ω")
        (field (name "POWER RATING") "0.1W")
      )
      (libsource (lib "Inverter_25kW") (part "ERJ-3EKF49R9V"))
    )
    (comp (ref "R121")
      (value "ERJ-3EKF49R9V")
      (footprint "FP-MCR03-IPC_B")
      (description "RES SMD 49.9 OHM 1% 1/10W 0603")
      (fields
        (field (name "MANUFACTURER") "PANASONIC")
        (field (name "TOLERANCE") "1%")
        (field (name "RESISTANCE") "49.9Ω")
        (field (name "POWER RATING") "0.1W")
      )
      (libsource (lib "Inverter_25kW") (part "ERJ-3EKF49R9V"))
    )
    (comp (ref "R122")
      (value "ERJ-3EKF49R9V")
      (footprint "FP-MCR03-IPC_B")
      (description "RES SMD 49.9 OHM 1% 1/10W 0603")
      (fields
        (field (name "MANUFACTURER") "PANASONIC")
        (field (name "TOLERANCE") "1%")
        (field (name "RESISTANCE") "49.9Ω")
        (field (name "POWER RATING") "0.1W")
      )
      (libsource (lib "Inverter_25kW") (part "ERJ-3EKF49R9V"))
    )
    (comp (ref "R123")
      (value "0.91Ω")
      (footprint "RESC3125X70X40NL20T20")
      (description "RES 0.91 OHM 1% 1W 1210")
      (fields
        (field (name "MANUFACTURER") "VISHAY DALE")
        (field (name "PART NUMBER") "RCWE1210R910FKEA")
        (field (name "POWER") "1W")
      )
      (libsource (lib "Altium Content Vault") (part "RES"))
    )
    (comp (ref "R124")
      (value "0Ω")
      (footprint "RESC3125X70X40NL20T20")
      (description "RES SMD 0 OHM JUMPER 3/4W 1210")
      (fields
        (field (name "MANUFACTURER") "VISHAY DALE")
        (field (name "MANUFACTURER PART NUMBER") "CRCW12100000Z0EAHP")
        (field (name "POWER RATING") "0.75W")
      )
      (libsource (lib "CRD25DA12N-FMC") (part "CRCW12100000Z0EAHP"))
    )
    (comp (ref "R197")
      (value "RC0603FR-07100KL")
      (footprint "FP-MCR03-IPC_B")
      (description "RES 100K OHM 1% 1/10W 0603")
      (fields
        (field (name "MANUFACTURER") "YAGEO")
        (field (name "TOLERANCE") "1%")
        (field (name "RESISTANCE") "100kΩ")
        (field (name "POWER RATING") "0.1W")
      )
      (libsource (lib "Inverter_25kW") (part "RC0603FR-07100KL"))
    )
    (comp (ref "R198")
      (value "RC0603FR-07100KL")
      (footprint "FP-MCR03-IPC_B")
      (description "RES 100K OHM 1% 1/10W 0603")
      (fields
        (field (name "MANUFACTURER") "YAGEO")
        (field (name "TOLERANCE") "1%")
        (field (name "RESISTANCE") "100kΩ")
        (field (name "POWER RATING") "0.1W")
      )
      (libsource (lib "Inverter_25kW") (part "RC0603FR-07100KL"))
    )
    (comp (ref "R199")
      (value "RC0603FR-07100KL")
      (footprint "FP-MCR03-IPC_B")
      (description "RES 100K OHM 1% 1/10W 0603")
      (fields
        (field (name "MANUFACTURER") "YAGEO")
        (field (name "TOLERANCE") "1%")
        (field (name "RESISTANCE") "100kΩ")
        (field (name "POWER RATING") "0.1W")
      )
      (libsource (lib "Inverter_25kW") (part "RC0603FR-07100KL"))
    )
    (comp (ref "R200")
      (value "RC0603FR-07100KL")
      (footprint "FP-MCR03-IPC_B")
      (description "RES 100K OHM 1% 1/10W 0603")
      (fields
        (field (name "MANUFACTURER") "YAGEO")
        (field (name "TOLERANCE") "1%")
        (field (name "RESISTANCE") "100kΩ")
        (field (name "POWER RATING") "0.1W")
      )
      (libsource (lib "Inverter_25kW") (part "RC0603FR-07100KL"))
    )
    (comp (ref "R201")
      (value "RC0603FR-07100KL")
      (footprint "FP-MCR03-IPC_B")
      (description "RES 100K OHM 1% 1/10W 0603")
      (fields
        (field (name "MANUFACTURER") "YAGEO")
        (field (name "TOLERANCE") "1%")
        (field (name "RESISTANCE") "100kΩ")
        (field (name "POWER RATING") "0.1W")
      )
      (libsource (lib "Inverter_25kW") (part "RC0603FR-07100KL"))
    )
    (comp (ref "R202")
      (value "RC0603FR-07100KL")
      (footprint "FP-MCR03-IPC_B")
      (description "RES 100K OHM 1% 1/10W 0603")
      (fields
        (field (name "MANUFACTURER") "YAGEO")
        (field (name "TOLERANCE") "1%")
        (field (name "RESISTANCE") "100kΩ")
        (field (name "POWER RATING") "0.1W")
      )
      (libsource (lib "Inverter_25kW") (part "RC0603FR-07100KL"))
    )
    (comp (ref "R203")
      (value "ERJ3EKF1002V")
      (footprint "FP-MCR03-IPC_B")
      (description "RES SMD 10K OHM 1% 1/10W 0603")
      (fields
        (field (name "MANUFACTURER") "PANASONIC")
        (field (name "MANUFACTURER PART NUMBER") "ERJ-3EKF1002V")
        (field (name "RESISTANCE") "10kΩ")
        (field (name "MAX POWER DISSIPATION") "0.1W")
      )
      (libsource (lib "Inverter_25kW") (part "ERJ3EKF1002V"))
    )
    (comp (ref "U8")
      (value "ISO722MDR")
      (footprint "D0008B_L")
      (description "DGTL ISO 2500VRMS 1CH GP 8SOIC")
      (fields (field (name "MANUFACTURER") "TEXAS INSTRUMENTS"))
      (libsource (lib "CRD25DA12N-FMC") (part "CMP-0328-00055-4"))
    )
    (comp (ref "U9")
      (value "TS431IYLT")
      (footprint "SOT95P280X145-5N")
      (description "IC VREF SHUNT ADJ 2% SOT23-5")
      (fields
        (field (name "MANUFACTURER") "STMICROELECTRONICS")
        (field (name "TOLERANCE") "2%")
        (field (name "MANUFACTURER PRINT") "ST")
      )
      (libsource (lib "Inverter_25kW") (part "TS431IYLT"))
    )
    (comp (ref "U10")
      (value "MCP6292-E/MS")
      (footprint "MSOP-MS8_L")
      (description "IC OPAMP GP 2 CIRCUIT 8MSOP")
      (fields (field (name "MANUFACTURER") "MICROCHIP") (field (name "MANUFACTURER PRINT") "MICROCHIP"))
      (libsource (lib "Inverter_25kW") (part "MCP6292-E/MS"))
    )
    (comp (ref "U11")
      (value "LTC6992CS6-2#TRMPBF")
      (footprint "SOT95P280X100-6N")
      (description "IC OSC SILICON PROG TSOT23-6")
      (fields
        (field (name "MANUFACTURER") "ANALOG DEVICES")
        (field (name "MANUFACTURER PRINT") "ANALOG DEVICES")
      )
      (libsource (lib "Inverter_25kW") (part "LTC6992CS6-2#TRMPBF"))
    )
    (comp (ref "U13")
      (value "SN74LV541ATPWR")
      (footprint "PW0020A_L")
      (description "IC BUF NON-INVERT 5.5V 20TSSOP")
      (fields
        (field (name "GENERIC PART NUMBER") "SN74LV541AT")
        (field (name "MANUFACTURER") "TEXAS INSTRUMENTS")
        (field (name "MANUFACTURER PART NUMBER") "SN74LV541ATPWR")
      )
      (libsource (lib "Altium Content Vault") (part "TI-SN54_74_CD74XXXX541XX-20"))
    )
    (comp (ref "U14")
      (value "UCC5350SBD")
      (footprint "D0008B_HV")
      (description "5A/5A, 3-KVRMS SINGLE-CHANNEL IS")
      (fields
        (field (name "MANUFACTURER") "TEXAS INSTRUMENTS")
        (field (name "MANUFACTURER PRINT") "TEXAS INSTRUMENTS")
        (field (name "COPYRIGHT") "Copyright (C) 2021 Ultra Librarian. All rights reserved.")
      )
      (libsource (lib "Inverter_25kW") (part "UCC5350SBD"))
    )
    (comp (ref "U15")
      (value "UCC5350SBD")
      (footprint "D0008B_HV")
      (description "5A/5A, 3-KVRMS SINGLE-CHANNEL IS")
      (fields
        (field (name "MANUFACTURER") "TEXAS INSTRUMENTS")
        (field (name "MANUFACTURER PRINT") "TEXAS INSTRUMENTS")
        (field (name "COPYRIGHT") "Copyright (C) 2021 Ultra Librarian. All rights reserved.")
      )
      (libsource (lib "Inverter_25kW") (part "UCC5350SBD"))
    )
    (comp (ref "U16")
      (value "MGJ2D121503SC")
      (footprint "Inverter_25kW:MGJ2D121509SC")
      (description "DC DC CONVERTER 15V -3V 1.7W")
      (fields (field (name "MANUFACTURER") "MURATA") (field (name "MANUFACTURER PRINT") "MURATA"))
      (libsource (lib "Inverter_25kW") (part "MGJ2D121503SC"))
    )
    (comp (ref "U17")
      (value "MGJ2D121503SC")
      (footprint "Inverter_25kW:MGJ2D121509SC")
      (description "DC DC CONVERTER 15V -3V 1.7W")
      (fields (field (name "MANUFACTURER") "MURATA") (field (name "MANUFACTURER PRINT") "MURATA"))
      (libsource (lib "Inverter_25kW") (part "MGJ2D121503SC"))
    )
    (comp (ref "U20")
      (value "UCC5350SBD")
      (footprint "D0008B_HV")
      (description "5A/5A, 3-KVRMS SINGLE-CHANNEL IS")
      (fields
        (field (name "MANUFACTURER") "TEXAS INSTRUMENTS")
        (field (name "MANUFACTURER PRINT") "TEXAS INSTRUMENTS")
        (field (name "COPYRIGHT") "Copyright (C) 2021 Ultra Librarian. All rights reserved.")
      )
      (libsource (lib "Inverter_25kW") (part "UCC5350SBD"))
    )
    (comp (ref "U22")
      (value "UCC5350SBD")
      (footprint "D0008B_HV")
      (description "5A/5A, 3-KVRMS SINGLE-CHANNEL IS")
      (fields
        (field (name "MANUFACTURER") "TEXAS INSTRUMENTS")
        (field (name "MANUFACTURER PRINT") "TEXAS INSTRUMENTS")
        (field (name "COPYRIGHT") "Copyright (C) 2021 Ultra Librarian. All rights reserved.")
      )
      (libsource (lib "Inverter_25kW") (part "UCC5350SBD"))
    )
    (comp (ref "U24")
      (value "MGJ2D121503SC")
      (footprint "Inverter_25kW:MGJ2D121509SC")
      (description "DC DC CONVERTER 15V -3V 1.7W")
      (fields (field (name "MANUFACTURER") "MURATA") (field (name "MANUFACTURER PRINT") "MURATA"))
      (libsource (lib "Inverter_25kW") (part "MGJ2D121503SC"))
    )
    (comp (ref "U25")
      (value "MGJ2D121503SC")
      (footprint "Inverter_25kW:MGJ2D121509SC")
      (description "DC DC CONVERTER 15V -3V 1.7W")
      (fields (field (name "MANUFACTURER") "MURATA") (field (name "MANUFACTURER PRINT") "MURATA"))
      (libsource (lib "Inverter_25kW") (part "MGJ2D121503SC"))
    )
    (comp (ref "U26")
      (value "UCC5350SBD")
      (footprint "D0008B_HV")
      (description "5A/5A, 3-KVRMS SINGLE-CHANNEL IS")
      (fields
        (field (name "MANUFACTURER") "TEXAS INSTRUMENTS")
        (field (name "MANUFACTURER PRINT") "TEXAS INSTRUMENTS")
        (field (name "COPYRIGHT") "Copyright (C) 2021 Ultra Librarian. All rights reserved.")
      )
      (libsource (lib "Inverter_25kW") (part "UCC5350SBD"))
    )
    (comp (ref "U27")
      (value "UCC5350SBD")
      (footprint "D0008B_HV")
      (description "5A/5A, 3-KVRMS SINGLE-CHANNEL IS")
      (fields
        (field (name "MANUFACTURER") "TEXAS INSTRUMENTS")
        (field (name "MANUFACTURER PRINT") "TEXAS INSTRUMENTS")
        (field (name "COPYRIGHT") "Copyright (C) 2021 Ultra Librarian. All rights reserved.")
      )
      (libsource (lib "Inverter_25kW") (part "UCC5350SBD"))
    )
    (comp (ref "U28")
      (value "MGJ2D121503SC")
      (footprint "Inverter_25kW:MGJ2D121509SC")
      (description "DC DC CONVERTER 15V -3V 1.7W")
      (fields (field (name "MANUFACTURER") "MURATA") (field (name "MANUFACTURER PRINT") "MURATA"))
      (libsource (lib "Inverter_25kW") (part "MGJ2D121503SC"))
    )
    (comp (ref "U29")
      (value "MGJ2D121503SC")
      (footprint "Inverter_25kW:MGJ2D121509SC")
      (description "DC DC CONVERTER 15V -3V 1.7W")
      (fields (field (name "MANUFACTURER") "MURATA") (field (name "MANUFACTURER PRINT") "MURATA"))
      (libsource (lib "Inverter_25kW") (part "MGJ2D121503SC"))
    )
  )
  (nets
    (net (code "1") (name "+3.3V") (class "Default")
      (node (ref "C131") (pin "1") (pinfunction "1_1") (pintype "passive"))
      (node (ref "U8") (pin "8") (pinfunction "VCC2_8") (pintype "power_in"))
    )
    (net (code "2") (name "+5V") (class "Default")
      (node (ref "C144") (pin "1") (pinfunction "1_1") (pintype "passive"))
      (node (ref "C29") (pin "1") (pinfunction "1_1") (pintype "passive"))
      (node (ref "C39") (pin "1") (pinfunction "1_1") (pintype "passive"))
      (node (ref "C51") (pin "1") (pinfunction "1_1") (pintype "passive"))
      (node (ref "C65") (pin "1") (pinfunction "1_1") (pintype "passive"))
      (node (ref "C76") (pin "1") (pinfunction "1_1") (pintype "passive"))
      (node (ref "C86") (pin "1") (pinfunction "1_1") (pintype "passive"))
      (node (ref "U13") (pin "20") (pinfunction "VCC_20") (pintype "power_in"))
      (node (ref "U15") (pin "1") (pinfunction "VCC1_1") (pintype "power_in"))
      (node (ref "U22") (pin "1") (pinfunction "VCC1_1") (pintype "power_in"))
      (node (ref "U27") (pin "1") (pinfunction "VCC1_1") (pintype "power_in"))
    )
    (net (code "3") (name "+5V_ALT") (class "Default")
      (node (ref "C28") (pin "1") (pinfunction "1_1") (pintype "passive"))
      (node (ref "C38") (pin "1") (pinfunction "1_1") (pintype "passive"))
      (node (ref "C50") (pin "1") (pinfunction "1_1") (pintype "passive"))
      (node (ref "C64") (pin "1") (pinfunction "1_1") (pintype "passive"))
      (node (ref "C75") (pin "1") (pinfunction "1_1") (pintype "passive"))
      (node (ref "C85") (pin "1") (pinfunction "1_1") (pintype "passive"))
      (node (ref "U14") (pin "1") (pinfunction "VCC1_1") (pintype "power_in"))
      (node (ref "U20") (pin "1") (pinfunction "VCC1_1") (pintype "power_in"))
      (node (ref "U26") (pin "1") (pinfunction "VCC1_1") (pintype "power_in"))
    )
    (net (code "4") (name "+5V_NTC") (class "Default")
      (node (ref "C15") (pin "1") (pinfunction "1_1") (pintype "passive"))
      (node (ref "C16") (pin "1") (pinfunction "1_1") (pintype "passive"))
      (node (ref "C20") (pin "1") (pinfunction "1_1") (pintype "passive"))
      (node (ref "R48") (pin "2") (pinfunction "2_2") (pintype "passive"))
      (node (ref "R62") (pin "2") (pinfunction "2_2") (pintype "passive"))
      (node (ref "U10") (pin "8") (pinfunction "VDD_8") (pintype "power_in"))
      (node (ref "U11") (pin "5") (pinfunction "V+_5") (pintype "passive"))
      (node (ref "U8") (pin "1") (pinfunction "VCC1_1") (pintype "power_in"))
      (node (ref "U8") (pin "3") (pinfunction "VCC1_3") (pintype "power_in"))
    )
    (net (code "5") (name "+12V") (class "Default")
      (node (ref "L1") (pin "1") (pinfunction "1_1") (pintype "passive"))
      (node (ref "L2") (pin "1") (pinfunction "1_1") (pintype "passive"))
      (node (ref "L3") (pin "1") (pinfunction "1_1") (pintype "passive"))
      (node (ref "L4") (pin "1") (pinfunction "1_1") (pintype "passive"))
      (node (ref "L5") (pin "1") (pinfunction "1_1") (pintype "passive"))
      (node (ref "L6") (pin "1") (pinfunction "1_1") (pintype "passive"))
    )
    (net (code "6") (name "/+15V_U_HS") (class "Default")
      (node (ref "C62") (pin "1") (pinfunction "1_1") (pintype "passive"))
      (node (ref "C71") (pin "1") (pinfunction "1_1") (pintype "passive"))
      (node (ref "U20") (pin "5") (pinfunction "VCC2_5") (pintype "power_in"))
      (node (ref "U24") (pin "7") (pinfunction "+VOUT_7") (pintype "passive"))
    )
    (net (code "7") (name "/+15V_U_LS") (class "Default")
      (node (ref "C83") (pin "1") (pinfunction "1_1") (pintype "passive"))
      (node (ref "C89") (pin "1") (pinfunction "1_1") (pintype "passive"))
      (node (ref "U26") (pin "5") (pinfunction "VCC2_5") (pintype "power_in"))
      (node (ref "U28") (pin "7") (pinfunction "+VOUT_7") (pintype "passive"))
    )
    (net (code "8") (name "/+15V_V_HS") (class "Default")
      (node (ref "C36") (pin "1") (pinfunction "1_1") (pintype "passive"))
      (node (ref "C42") (pin "1") (pinfunction "1_1") (pintype "passive"))
      (node (ref "U14") (pin "5") (pinfunction "VCC2_5") (pintype "power_in"))
      (node (ref "U16") (pin "7") (pinfunction "+VOUT_7") (pintype "passive"))
    )
    (net (code "9") (name "/+15V_V_LS") (class "Default")
      (node (ref "C78") (pin "1") (pinfunction "1_1") (pintype "passive"))
      (node (ref "C90") (pin "1") (pinfunction "1_1") (pintype "passive"))
      (node (ref "U27") (pin "5") (pinfunction "VCC2_5") (pintype "power_in"))
      (node (ref "U29") (pin "7") (pinfunction "+VOUT_7") (pintype "passive"))
    )
    (net (code "10") (name "/+15V_W_HS") (class "Default")
      (node (ref "C31") (pin "1") (pinfunction "1_1") (pintype "passive"))
      (node (ref "C43") (pin "1") (pinfunction "1_1") (pintype "passive"))
      (node (ref "U15") (pin "5") (pinfunction "VCC2_5") (pintype "power_in"))
      (node (ref "U17") (pin "7") (pinfunction "+VOUT_7") (pintype "passive"))
    )
    (net (code "11") (name "/+15V_W_LS") (class "Default")
      (node (ref "C53") (pin "1") (pinfunction "1_1") (pintype "passive"))
      (node (ref "C72") (pin "1") (pinfunction "1_1") (pintype "passive"))
      (node (ref "U22") (pin "5") (pinfunction "VCC2_5") (pintype "power_in"))
      (node (ref "U25") (pin "7") (pinfunction "+VOUT_7") (pintype "passive"))
    )
    (net (code "12") (name "/-3V_U_HS") (class "Default")
      (node (ref "C52") (pin "2") (pinfunction "2_2") (pintype "passive"))
      (node (ref "C67") (pin "2") (pinfunction "2_2") (pintype "passive"))
      (node (ref "U20") (pin "8") (pinfunction "VEE2_8") (pintype "power_in"))
      (node (ref "U24") (pin "5") (pinfunction "-VOUT_5") (pintype "passive"))
    )
    (net (code "13") (name "/-3V_U_LS") (class "Default")
      (node (ref "C77") (pin "2") (pinfunction "2_2") (pintype "passive"))
      (node (ref "C87") (pin "2") (pinfunction "2_2") (pintype "passive"))
      (node (ref "U26") (pin "8") (pinfunction "VEE2_8") (pintype "power_in"))
      (node (ref "U28") (pin "5") (pinfunction "-VOUT_5") (pintype "passive"))
    )
    (net (code "14") (name "/-3V_V_HS") (class "Default")
      (node (ref "C30") (pin "2") (pinfunction "2_2") (pintype "passive"))
      (node (ref "C40") (pin "2") (pinfunction "2_2") (pintype "passive"))
      (node (ref "U14") (pin "8") (pinfunction "VEE2_8") (pintype "power_in"))
      (node (ref "U16") (pin "5") (pinfunction "-VOUT_5") (pintype "passive"))
    )
    (net (code "15") (name "/-3V_V_LS") (class "Default")
      (node (ref "C84") (pin "2") (pinfunction "2_2") (pintype "passive"))
      (node (ref "C88") (pin "2") (pinfunction "2_2") (pintype "passive"))
      (node (ref "U27") (pin "8") (pinfunction "VEE2_8") (pintype "power_in"))
      (node (ref "U29") (pin "5") (pinfunction "-VOUT_5") (pintype "passive"))
    )
    (net (code "16") (name "/-3V_W_HS") (class "Default")
      (node (ref "C37") (pin "2") (pinfunction "2_2") (pintype "passive"))
      (node (ref "C41") (pin "2") (pinfunction "2_2") (pintype "passive"))
      (node (ref "U15") (pin "8") (pinfunction "VEE2_8") (pintype "power_in"))
      (node (ref "U17") (pin "5") (pinfunction "-VOUT_5") (pintype "passive"))
    )
    (net (code "17") (name "/-3V_W_LS") (class "Default")
      (node (ref "C63") (pin "2") (pinfunction "2_2") (pintype "passive"))
      (node (ref "C68") (pin "2") (pinfunction "2_2") (pintype "passive"))
      (node (ref "U22") (pin "8") (pinfunction "VEE2_8") (pintype "power_in"))
      (node (ref "U25") (pin "5") (pinfunction "-VOUT_5") (pintype "passive"))
    )
    (net (code "18") (name "/G1H") (class "Default")
      (node (ref "R101") (pin "1") (pinfunction "1_1") (pintype "passive"))
      (node (ref "U20") (pin "6") (pinfunction "OUTH_6") (pintype "output"))
    )
    (net (code "19") (name "/G1L") (class "Default")
      (node (ref "R92") (pin "1") (pinfunction "1_1") (pintype "passive"))
      (node (ref "U20") (pin "7") (pinfunction "OUTL_7") (pintype "input"))
    )
    (net (code "20") (name "/G2H") (class "Default")
      (node (ref "R123") (pin "1") (pinfunction "1_1") (pintype "passive"))
      (node (ref "U26") (pin "6") (pinfunction "OUTH_6") (pintype "output"))
    )
    (net (code "21") (name "/G2L") (class "Default")
      (node (ref "R115") (pin "1") (pinfunction "1_1") (pintype "passive"))
      (node (ref "U26") (pin "7") (pinfunction "OUTL_7") (pintype "input"))
    )
    (net (code "22") (name "/G3H") (class "Default")
      (node (ref "R77") (pin "1") (pinfunction "1_1") (pintype "passive"))
      (node (ref "U14") (pin "6") (pinfunction "OUTH_6") (pintype "output"))
    )
    (net (code "23") (name "/G3L") (class "Default")
      (node (ref "R69") (pin "1") (pinfunction "1_1") (pintype "passive"))
      (node (ref "U14") (pin "7") (pinfunction "OUTL_7") (pintype "input"))
    )
    (net (code "24") (name "/G4H") (class "Default")
      (node (ref "R116") (pin "1") (pinfunction "1_1") (pintype "passive"))
      (node (ref "U27") (pin "6") (pinfunction "OUTH_6") (pintype "output"))
    )
    (net (code "25") (name "/G4L") (class "Default")
      (node (ref "R124") (pin "1") (pinfunction "1_1") (pintype "passive"))
      (node (ref "U27") (pin "7") (pinfunction "OUTL_7") (pintype "input"))
    )
    (net (code "26") (name "/G5H") (class "Default")
      (node (ref "R70") (pin "1") (pinfunction "1_1") (pintype "passive"))
      (node (ref "U15") (pin "6") (pinfunction "OUTH_6") (pintype "output"))
    )
    (net (code "27") (name "/G5L") (class "Default")
      (node (ref "R78") (pin "1") (pinfunction "1_1") (pintype "passive"))
      (node (ref "U15") (pin "7") (pinfunction "OUTL_7") (pintype "input"))
    )
    (net (code "28") (name "/G6H") (class "Default")
      (node (ref "R93") (pin "1") (pinfunction "1_1") (pintype "passive"))
      (node (ref "U22") (pin "6") (pinfunction "OUTH_6") (pintype "output"))
    )
    (net (code "29") (name "/G6L") (class "Default")
      (node (ref "R102") (pin "1") (pinfunction "1_1") (pintype "passive"))
      (node (ref "U22") (pin "7") (pinfunction "OUTL_7") (pintype "input"))
    )
    (net (code "30") (name "/GD_DIS_FILT") (class "Default")
      (node (ref "C143") (pin "1") (pinfunction "1_1") (pintype "passive"))
      (node (ref "R203") (pin "2") (pinfunction "2_2") (pintype "passive"))
      (node (ref "R81") (pin "2") (pinfunction "2_2") (pintype "passive"))
      (node (ref "U13") (pin "1") (pinfunction "~{OE1}_1") (pintype "input"))
      (node (ref "U13") (pin "19") (pinfunction "~{OE2}_19") (pintype "input"))
    )
    (net (code "31") (name "/NTC1_BUF") (class "Default")
      (node (ref "R59") (pin "1") (pinfunction "1_1") (pintype "passive"))
      (node (ref "U10") (pin "5") (pinfunction "VINB+_5") (pintype "input"))
    )
    (net (code "32") (name "/NTC1_FB") (class "Default")
      (node (ref "R53") (pin "2") (pinfunction "2_2") (pintype "passive"))
      (node (ref "R54") (pin "2") (pinfunction "2_2") (pintype "passive"))
      (node (ref "U10") (pin "7") (pinfunction "VOUTB_7") (pintype "output"))
    )
    (net (code "33") (name "/NTC1_INV") (class "Default")
      (node (ref "R52") (pin "2") (pinfunction "2_2") (pintype "passive"))
      (node (ref "R53") (pin "1") (pinfunction "1_1") (pintype "passive"))
      (node (ref "U10") (pin "6") (pinfunction "VINB-_6") (pintype "input"))
    )
    (net (code "34") (name "/NTC_B0") (class "Default")
      (node (ref "R47") (pin "2") (pinfunction "2_2") (pintype "passive"))
      (node (ref "R48") (pin "1") (pinfunction "1_1") (pintype "passive"))
      (node (ref "R49") (pin "2") (pinfunction "2_2") (pintype "passive"))
      (node (ref "U9") (pin "3") (pinfunction "3_3") (pintype "passive"))
    )
    (net (code "35") (name "/NTC_B1") (class "Default")
      (node (ref "R46") (pin "2") (pinfunction "2_2") (pintype "passive"))
      (node (ref "R47") (pin "1") (pinfunction "1_1") (pintype "passive"))
      (node (ref "U9") (pin "4") (pinfunction "4_4") (pintype "passive"))
    )
    (net (code "36") (name "/NTC_BIAS") (class "Default")
      (node (ref "C14") (pin "1") (pinfunction "1_1") (pintype "passive"))
      (node (ref "R49") (pin "1") (pinfunction "1_1") (pintype "passive"))
      (node (ref "R51") (pin "2") (pinfunction "2_2") (pintype "passive"))
      (node (ref "U10") (pin "3") (pinfunction "VINA+_3") (pintype "input"))
    )
    (net (code "37") (name "/NTC_BIAS_BUF") (class "Default")
      (node (ref "R56") (pin "2") (pinfunction "2_2") (pintype "passive"))
      (node (ref "U10") (pin "1") (pinfunction "VOUTA_1") (pintype "output"))
      (node (ref "U10") (pin "2") (pinfunction "VINA-_2") (pintype "input"))
    )
    (net (code "38") (name "/NTC_DIV") (class "Default")
      (node (ref "R61") (pin "2") (pinfunction "2_2") (pintype "passive"))
      (node (ref "R62") (pin "1") (pinfunction "1_1") (pintype "passive"))
      (node (ref "U11") (pin "4") (pinfunction "DIV_4") (pintype "passive"))
    )
    (net (code "39") (name "/NTC_MOD") (class "Default")
      (node (ref "C18") (pin "1") (pinfunction "1_1") (pintype "passive"))
      (node (ref "R54") (pin "1") (pinfunction "1_1") (pintype "passive"))
      (node (ref "U11") (pin "1") (pinfunction "MOD_1") (pintype "passive"))
    )
    (net (code "40") (name "/NTC_PWM") (class "Default")
      (node (ref "U11") (pin "6") (pinfunction "OUT_6") (pintype "passive"))
      (node (ref "U8") (pin "2") (pinfunction "IN_2") (pintype "input"))
    )
    (net (code "41") (name "/NTC_SET") (class "Default")
      (node (ref "R60") (pin "2") (pinfunction "2_2") (pintype "passive"))
      (node (ref "U11") (pin "3") (pinfunction "SET_3") (pintype "passive"))
    )
    (net (code "42") (name "/U_HS") (class "Default")
      (node (ref "R121") (pin "1") (pinfunction "1_1") (pintype "passive"))
      (node (ref "R197") (pin "2") (pinfunction "2_2") (pintype "passive"))
      (node (ref "R94") (pin "1") (pinfunction "1_1") (pintype "passive"))
      (node (ref "U13") (pin "14") (pinfunction "Y5_14") (pintype "tri_state"))
    )
    (net (code "43") (name "/U_HS+_FILT") (class "Default")
      (node (ref "C56") (pin "1") (pinfunction "1_1") (pintype "passive"))
      (node (ref "R94") (pin "2") (pinfunction "2_2") (pintype "passive"))
      (node (ref "U20") (pin "2") (pinfunction "IN+_2") (pintype "input"))
    )
    (net (code "44") (name "/U_HS-_FILT") (class "Default")
      (node (ref "C81") (pin "1") (pinfunction "1_1") (pintype "passive"))
      (node (ref "R121") (pin "2") (pinfunction "2_2") (pintype "passive"))
      (node (ref "U26") (pin "3") (pinfunction "IN-_3") (pintype "input"))
    )
    (net (code "45") (name "/U_LS") (class "Default")
      (node (ref "R118") (pin "1") (pinfunction "1_1") (pintype "passive"))
      (node (ref "R199") (pin "2") (pinfunction "2_2") (pintype "passive"))
      (node (ref "R98") (pin "1") (pinfunction "1_1") (pintype "passive"))
      (node (ref "U13") (pin "15") (pinfunction "Y4_15") (pintype "tri_state"))
    )
    (net (code "46") (name "/U_LS+_FILT") (class "Default")
      (node (ref "C79") (pin "1") (pinfunction "1_1") (pintype "passive"))
      (node (ref "R118") (pin "2") (pinfunction "2_2") (pintype "passive"))
      (node (ref "U26") (pin "2") (pinfunction "IN+_2") (pintype "input"))
    )
    (net (code "47") (name "/U_LS-_FILT") (class "Default")
      (node (ref "C59") (pin "1") (pinfunction "1_1") (pintype "passive"))
      (node (ref "R98") (pin "2") (pinfunction "2_2") (pintype "passive"))
      (node (ref "U20") (pin "3") (pinfunction "IN-_3") (pintype "input"))
    )
    (net (code "48") (name "/V_HS") (class "Default")
      (node (ref "R119") (pin "1") (pinfunction "1_1") (pintype "passive"))
      (node (ref "R201") (pin "2") (pinfunction "2_2") (pintype "passive"))
      (node (ref "R71") (pin "1") (pinfunction "1_1") (pintype "passive"))
      (node (ref "U13") (pin "17") (pinfunction "Y2_17") (pintype "tri_state"))
    )
    (net (code "49") (name "/V_HS+_FILT") (class "Default")
      (node (ref "C32") (pin "1") (pinfunction "1_1") (pintype "passive"))
      (node (ref "R71") (pin "2") (pinfunction "2_2") (pintype "passive"))
      (node (ref "U14") (pin "2") (pinfunction "IN+_2") (pintype "input"))
    )
    (net (code "50") (name "/V_HS-_FILT") (class "Default")
      (node (ref "C80") (pin "1") (pinfunction "1_1") (pintype "passive"))
      (node (ref "R119") (pin "2") (pinfunction "2_2") (pintype "passive"))
      (node (ref "U27") (pin "3") (pinfunction "IN-_3") (pintype "input"))
    )
    (net (code "51") (name "/V_LS") (class "Default")
      (node (ref "R122") (pin "1") (pinfunction "1_1") (pintype "passive"))
      (node (ref "R202") (pin "2") (pinfunction "2_2") (pintype "passive"))
      (node (ref "R75") (pin "1") (pinfunction "1_1") (pintype "passive"))
      (node (ref "U13") (pin "18") (pinfunction "Y1_18") (pintype "tri_state"))
    )
    (net (code "52") (name "/V_LS+_FILT") (class "Default")
      (node (ref "C82") (pin "1") (pinfunction "1_1") (pintype "passive"))
      (node (ref "R122") (pin "2") (pinfunction "2_2") (pintype "passive"))
      (node (ref "U27") (pin "2") (pinfunction "IN+_2") (pintype "input"))
    )
    (net (code "53") (name "/V_LS-_FILT") (class "Default")
      (node (ref "C34") (pin "1") (pinfunction "1_1") (pintype "passive"))
      (node (ref "R75") (pin "2") (pinfunction "2_2") (pintype "passive"))
      (node (ref "U14") (pin "3") (pinfunction "IN-_3") (pintype "input"))
    )
    (net (code "54") (name "/W_HS") (class "Default")
      (node (ref "R198") (pin "2") (pinfunction "2_2") (pintype "passive"))
      (node (ref "R76") (pin "1") (pinfunction "1_1") (pintype "passive"))
      (node (ref "R95") (pin "1") (pinfunction "1_1") (pintype "passive"))
      (node (ref "U13") (pin "11") (pinfunction "Y8_11") (pintype "tri_state"))
    )
    (net (code "55") (name "/W_HS+_FILT") (class "Default")
      (node (ref "C35") (pin "1") (pinfunction "1_1") (pintype "passive"))
      (node (ref "R76") (pin "2") (pinfunction "2_2") (pintype "passive"))
      (node (ref "U15") (pin "2") (pinfunction "IN+_2") (pintype "input"))
    )
    (net (code "56") (name "/W_HS-_FILT") (class "Default")
      (node (ref "C57") (pin "1") (pinfunction "1_1") (pintype "passive"))
      (node (ref "R95") (pin "2") (pinfunction "2_2") (pintype "passive"))
      (node (ref "U22") (pin "3") (pinfunction "IN-_3") (pintype "input"))
    )
    (net (code "57") (name "/W_LS") (class "Default")
      (node (ref "R200") (pin "2") (pinfunction "2_2") (pintype "passive"))
      (node (ref "R72") (pin "1") (pinfunction "1_1") (pintype "passive"))
      (node (ref "R99") (pin "1") (pinfunction "1_1") (pintype "passive"))
      (node (ref "U13") (pin "12") (pinfunction "Y7_12") (pintype "tri_state"))
    )
    (net (code "58") (name "/W_LS+_FILT") (class "Default")
      (node (ref "C60") (pin "1") (pinfunction "1_1") (pintype "passive"))
      (node (ref "R99") (pin "2") (pinfunction "2_2") (pintype "passive"))
      (node (ref "U22") (pin "2") (pinfunction "IN+_2") (pintype "input"))
    )
    (net (code "59") (name "/W_LS-_FILT") (class "Default")
      (node (ref "C33") (pin "1") (pinfunction "1_1") (pintype "passive"))
      (node (ref "R72") (pin "2") (pinfunction "2_2") (pintype "passive"))
      (node (ref "U15") (pin "3") (pinfunction "IN-_3") (pintype "input"))
    )
    (net (code "60") (name "G1") (class "Default")
      (node (ref "R101") (pin "2") (pinfunction "2_2") (pintype "passive"))
      (node (ref "R88") (pin "2") (pinfunction "2_2") (pintype "passive"))
      (node (ref "R92") (pin "2") (pinfunction "2_2") (pintype "passive"))
    )
    (net (code "61") (name "G2") (class "Default")
      (node (ref "R112") (pin "2") (pinfunction "2_2") (pintype "passive"))
      (node (ref "R115") (pin "2") (pinfunction "2_2") (pintype "passive"))
      (node (ref "R123") (pin "2") (pinfunction "2_2") (pintype "passive"))
    )
    (net (code "62") (name "G3") (class "Default")
      (node (ref "R67") (pin "2") (pinfunction "2_2") (pintype "passive"))
      (node (ref "R69") (pin "2") (pinfunction "2_2") (pintype "passive"))
      (node (ref "R77") (pin "2") (pinfunction "2_2") (pintype "passive"))
    )
    (net (code "63") (name "G4") (class "Default")
      (node (ref "R113") (pin "2") (pinfunction "2_2") (pintype "passive"))
      (node (ref "R116") (pin "2") (pinfunction "2_2") (pintype "passive"))
      (node (ref "R124") (pin "2") (pinfunction "2_2") (pintype "passive"))
    )
    (net (code "64") (name "G5") (class "Default")
      (node (ref "R68") (pin "2") (pinfunction "2_2") (pintype "passive"))
      (node (ref "R70") (pin "2") (pinfunction "2_2") (pintype "passive"))
      (node (ref "R78") (pin "2") (pinfunction "2_2") (pintype "passive"))
    )
    (net (code "65") (name "G6") (class "Default")
      (node (ref "R102") (pin "2") (pinfunction "2_2") (pintype "passive"))
      (node (ref "R89") (pin "2") (pinfunction "2_2") (pintype "passive"))
      (node (ref "R93") (pin "2") (pinfunction "2_2") (pintype "passive"))
    )
    (net (code "66") (name "GD_DIS") (class "Default")
      (node (ref "R81") (pin "1") (pinfunction "1_1") (pintype "passive"))
    )
    (net (code "67") (name "GND") (class "Default")
      (node (ref "C131") (pin "2") (pinfunction "2_2") (pintype "passive"))
      (node (ref "C143") (pin "2") (pinfunction "2_2") (pintype "passive"))
      (node (ref "C144") (pin "2") (pinfunction "2_2") (pintype "passive"))
      (node (ref "C28") (pin "2") (pinfunction "2_2") (pintype "passive"))
      (node (ref "C29") (pin "2") (pinfunction "2_2") (pintype "passive"))
      (node (ref "C32") (pin "2") (pinfunction "2_2") (pintype "passive"))
      (node (ref "C33") (pin "2") (pinfunction "2_2") (pintype "passive"))
      (node (ref "C34") (pin "2") (pinfunction "2_2") (pintype "passive"))
      (node (ref "C35") (pin "2") (pinfunction "2_2") (pintype "passive"))
      (node (ref "C38") (pin "2") (pinfunction "2_2") (pintype "passive"))
      (node (ref "C39") (pin "2") (pinfunction "2_2") (pintype "passive"))
      (node (ref "C50") (pin "2") (pinfunction "2_2") (pintype "passive"))
      (node (ref "C51") (pin "2") (pinfunction "2_2") (pintype "passive"))
      (node (ref "C56") (pin "2") (pinfunction "2_2") (pintype "passive"))
      (node (ref "C57") (pin "2") (pinfunction "2_2") (pintype "passive"))
      (node (ref "C59") (pin "2") (pinfunction "2_2") (pintype "passive"))
      (node (ref "C60") (pin "2") (pinfunction "2_2") (pintype "passive"))
      (node (ref "C64") (pin "2") (pinfunction "2_2") (pintype "passive"))
      (node (ref "C65") (pin "2") (pinfunction "2_2") (pintype "passive"))
      (node (ref "C75") (pin "2") (pinfunction "2_2") (pintype "passive"))
      (node (ref "C76") (pin "2") (pinfunction "2_2") (pintype "passive"))
      (node (ref "C79") (pin "2") (pinfunction "2_2") (pintype "passive"))
      (node (ref "C80") (pin "2") (pinfunction "2_2") (pintype "passive"))
      (node (ref "C81") (pin "2") (pinfunction "2_2") (pintype "passive"))
      (node (ref "C82") (pin "2") (pinfunction "2_2") (pintype "passive"))
      (node (ref "C85") (pin "2") (pinfunction "2_2") (pintype "passive"))
      (node (ref "C86") (pin "2") (pinfunction "2_2") (pintype "passive"))
      (node (ref "L1") (pin "2") (pinfunction "2_2") (pintype "passive"))
      (node (ref "L2") (pin "2") (pinfunction "2_2") (pintype "passive"))
      (node (ref "L3") (pin "2") (pinfunction "2_2") (pintype "passive"))
      (node (ref "L4") (pin "2") (pinfunction "2_2") (pintype "passive"))
      (node (ref "L5") (pin "2") (pinfunction "2_2") (pintype "passive"))
      (node (ref "L6") (pin "2") (pinfunction "2_2") (pintype "passive"))
      (node (ref "R197") (pin "1") (pinfunction "1_1") (pintype "passive"))
      (node (ref "R198") (pin "1") (pinfunction "1_1") (pintype "passive"))
      (node (ref "R199") (pin "1") (pinfunction "1_1") (pintype "passive"))
      (node (ref "R200") (pin "1") (pinfunction "1_1") (pintype "passive"))
      (node (ref "R201") (pin "1") (pinfunction "1_1") (pintype "passive"))
      (node (ref "R202") (pin "1") (pinfunction "1_1") (pintype "passive"))
      (node (ref "R203") (pin "1") (pinfunction "1_1") (pintype "passive"))
      (node (ref "U13") (pin "10") (pinfunction "GND_10") (pintype "power_in"))
      (node (ref "U13") (pin "4") (pinfunction "A3_4") (pintype "input"))
      (node (ref "U13") (pin "7") (pinfunction "A6_7") (pintype "input"))
      (node (ref "U14") (pin "4") (pinfunction "GND1_4") (pintype "power_in"))
      (node (ref "U15") (pin "4") (pinfunction "GND1_4") (pintype "power_in"))
      (node (ref "U20") (pin "4") (pinfunction "GND1_4") (pintype "power_in"))
      (node (ref "U22") (pin "4") (pinfunction "GND1_4") (pintype "power_in"))
      (node (ref "U26") (pin "4") (pinfunction "GND1_4") (pintype "power_in"))
      (node (ref "U27") (pin "4") (pinfunction "GND1_4") (pintype "power_in"))
      (node (ref "U8") (pin "5") (pinfunction "GND2_5") (pintype "power_in"))
      (node (ref "U8") (pin "7") (pinfunction "~{EN}_7") (pintype "input"))
    )
    (net (code "68") (name "GND_NTC") (class "Default")
      (node (ref "C14") (pin "2") (pinfunction "2_2") (pintype "passive"))
      (node (ref "C15") (pin "2") (pinfunction "2_2") (pintype "passive"))
      (node (ref "C16") (pin "2") (pinfunction "2_2") (pintype "passive"))
      (node (ref "C18") (pin "2") (pinfunction "2_2") (pintype "passive"))
      (node (ref "C20") (pin "2") (pinfunction "2_2") (pintype "passive"))
      (node (ref "R46") (pin "1") (pinfunction "1_1") (pintype "passive"))
      (node (ref "R51") (pin "1") (pinfunction "1_1") (pintype "passive"))
      (node (ref "R52") (pin "1") (pinfunction "1_1") (pintype "passive"))
      (node (ref "R60") (pin "1") (pinfunction "1_1") (pintype "passive"))
      (node (ref "R61") (pin "1") (pinfunction "1_1") (pintype "passive"))
      (node (ref "U10") (pin "4") (pinfunction "VSS_4") (pintype "power_in"))
      (node (ref "U11") (pin "2") (pinfunction "GND_2") (pintype "passive"))
      (node (ref "U8") (pin "4") (pinfunction "GND1_4") (pintype "power_in"))
      (node (ref "U9") (pin "5") (pinfunction "5_5") (pintype "passive"))
    )
    (net (code "69") (name "NTC1") (class "Default")
      (node (ref "R56") (pin "1") (pinfunction "1_1") (pintype "passive"))
      (node (ref "R59") (pin "2") (pinfunction "2_2") (pintype "passive"))
    )
    (net (code "70") (name "NTC_ISO") (class "Default")
      (node (ref "U8") (pin "6") (pinfunction "OUT_6") (pintype "tri_state"))
    )
    (net (code "71") (name "Net-(U16-+VIN)") (class "Default")
      (node (ref "C48") (pin "1") (pinfunction "1_1") (pintype "passive"))
      (node (ref "L1") (pin "4") (pinfunction "4_4") (pintype "passive"))
      (node (ref "U16") (pin "1") (pinfunction "+VIN_1") (pintype "passive"))
    )
    (net (code "72") (name "Net-(U16--VIN)") (class "Default")
      (node (ref "C48") (pin "2") (pinfunction "2_2") (pintype "passive"))
      (node (ref "L1") (pin "3") (pinfunction "3_3") (pintype "passive"))
      (node (ref "U16") (pin "2") (pinfunction "-VIN_2") (pintype "passive"))
    )
    (net (code "73") (name "Net-(U17-+VIN)") (class "Default")
      (node (ref "C49") (pin "1") (pinfunction "1_1") (pintype "passive"))
      (node (ref "L2") (pin "4") (pinfunction "4_4") (pintype "passive"))
      (node (ref "U17") (pin "1") (pinfunction "+VIN_1") (pintype "passive"))
    )
    (net (code "74") (name "Net-(U17--VIN)") (class "Default")
      (node (ref "C49") (pin "2") (pinfunction "2_2") (pintype "passive"))
      (node (ref "L2") (pin "3") (pinfunction "3_3") (pintype "passive"))
      (node (ref "U17") (pin "2") (pinfunction "-VIN_2") (pintype "passive"))
    )
    (net (code "75") (name "Net-(U24-+VIN)") (class "Default")
      (node (ref "C73") (pin "1") (pinfunction "1_1") (pintype "passive"))
      (node (ref "L3") (pin "4") (pinfunction "4_4") (pintype "passive"))
      (node (ref "U24") (pin "1") (pinfunction "+VIN_1") (pintype "passive"))
    )
    (net (code "76") (name "Net-(U24--VIN)") (class "Default")
      (node (ref "C73") (pin "2") (pinfunction "2_2") (pintype "passive"))
      (node (ref "L3") (pin "3") (pinfunction "3_3") (pintype "passive"))
      (node (ref "U24") (pin "2") (pinfunction "-VIN_2") (pintype "passive"))
    )
    (net (code "77") (name "Net-(U25-+VIN)") (class "Default")
      (node (ref "C74") (pin "1") (pinfunction "1_1") (pintype "passive"))
      (node (ref "L4") (pin "4") (pinfunction "4_4") (pintype "passive"))
      (node (ref "U25") (pin "1") (pinfunction "+VIN_1") (pintype "passive"))
    )
    (net (code "78") (name "Net-(U25--VIN)") (class "Default")
      (node (ref "C74") (pin "2") (pinfunction "2_2") (pintype "passive"))
      (node (ref "L4") (pin "3") (pinfunction "3_3") (pintype "passive"))
      (node (ref "U25") (pin "2") (pinfunction "-VIN_2") (pintype "passive"))
    )
    (net (code "79") (name "Net-(U28-+VIN)") (class "Default")
      (node (ref "C91") (pin "1") (pinfunction "1_1") (pintype "passive"))
      (node (ref "L5") (pin "4") (pinfunction "4_4") (pintype "passive"))
      (node (ref "U28") (pin "1") (pinfunction "+VIN_1") (pintype "passive"))
    )
    (net (code "80") (name "Net-(U28--VIN)") (class "Default")
      (node (ref "C91") (pin "2") (pinfunction "2_2") (pintype "passive"))
      (node (ref "L5") (pin "3") (pinfunction "3_3") (pintype "passive"))
      (node (ref "U28") (pin "2") (pinfunction "-VIN_2") (pintype "passive"))
    )
    (net (code "81") (name "Net-(U29-+VIN)") (class "Default")
      (node (ref "C92") (pin "1") (pinfunction "1_1") (pintype "passive"))
      (node (ref "L6") (pin "4") (pinfunction "4_4") (pintype "passive"))
      (node (ref "U29") (pin "1") (pinfunction "+VIN_1") (pintype "passive"))
    )
    (net (code "82") (name "Net-(U29--VIN)") (class "Default")
      (node (ref "C92") (pin "2") (pinfunction "2_2") (pintype "passive"))
      (node (ref "L6") (pin "3") (pinfunction "3_3") (pintype "passive"))
      (node (ref "U29") (pin "2") (pinfunction "-VIN_2") (pintype "passive"))
    )
    (net (code "83") (name "S1") (class "Default")
      (node (ref "C52") (pin "1") (pinfunction "1_1") (pintype "passive"))
      (node (ref "C62") (pin "2") (pinfunction "2_2") (pintype "passive"))
      (node (ref "C67") (pin "1") (pinfunction "1_1") (pintype "passive"))
      (node (ref "C71") (pin "2") (pinfunction "2_2") (pintype "passive"))
      (node (ref "R88") (pin "1") (pinfunction "1_1") (pintype "passive"))
      (node (ref "U24") (pin "6") (pinfunction "0V_6") (pintype "passive"))
    )
    (net (code "84") (name "S2") (class "Default")
      (node (ref "C77") (pin "1") (pinfunction "1_1") (pintype "passive"))
      (node (ref "C83") (pin "2") (pinfunction "2_2") (pintype "passive"))
      (node (ref "C87") (pin "1") (pinfunction "1_1") (pintype "passive"))
      (node (ref "C89") (pin "2") (pinfunction "2_2") (pintype "passive"))
      (node (ref "R112") (pin "1") (pinfunction "1_1") (pintype "passive"))
      (node (ref "U28") (pin "6") (pinfunction "0V_6") (pintype "passive"))
    )
    (net (code "85") (name "S3") (class "Default")
      (node (ref "C30") (pin "1") (pinfunction "1_1") (pintype "passive"))
      (node (ref "C36") (pin "2") (pinfunction "2_2") (pintype "passive"))
      (node (ref "C40") (pin "1") (pinfunction "1_1") (pintype "passive"))
      (node (ref "C42") (pin "2") (pinfunction "2_2") (pintype "passive"))
      (node (ref "R67") (pin "1") (pinfunction "1_1") (pintype "passive"))
      (node (ref "U16") (pin "6") (pinfunction "0V_6") (pintype "passive"))
    )
    (net (code "86") (name "S4") (class "Default")
      (node (ref "C78") (pin "2") (pinfunction "2_2") (pintype "passive"))
      (node (ref "C84") (pin "1") (pinfunction "1_1") (pintype "passive"))
      (node (ref "C88") (pin "1") (pinfunction "1_1") (pintype "passive"))
      (node (ref "C90") (pin "2") (pinfunction "2_2") (pintype "passive"))
      (node (ref "R113") (pin "1") (pinfunction "1_1") (pintype "passive"))
      (node (ref "U29") (pin "6") (pinfunction "0V_6") (pintype "passive"))
    )
    (net (code "87") (name "S5") (class "Default")
      (node (ref "C31") (pin "2") (pinfunction "2_2") (pintype "passive"))
      (node (ref "C37") (pin "1") (pinfunction "1_1") (pintype "passive"))
      (node (ref "C41") (pin "1") (pinfunction "1_1") (pintype "passive"))
      (node (ref "C43") (pin "2") (pinfunction "2_2") (pintype "passive"))
      (node (ref "R68") (pin "1") (pinfunction "1_1") (pintype "passive"))
      (node (ref "U17") (pin "6") (pinfunction "0V_6") (pintype "passive"))
    )
    (net (code "88") (name "S6") (class "Default")
      (node (ref "C53") (pin "2") (pinfunction "2_2") (pintype "passive"))
      (node (ref "C63") (pin "1") (pinfunction "1_1") (pintype "passive"))
      (node (ref "C68") (pin "1") (pinfunction "1_1") (pintype "passive"))
      (node (ref "C72") (pin "2") (pinfunction "2_2") (pintype "passive"))
      (node (ref "R89") (pin "1") (pinfunction "1_1") (pintype "passive"))
      (node (ref "U25") (pin "6") (pinfunction "0V_6") (pintype "passive"))
    )
    (net (code "89") (name "U_HS_PWM") (class "Default")
      (node (ref "U13") (pin "6") (pinfunction "A5_6") (pintype "input"))
    )
    (net (code "90") (name "U_LS_PWM") (class "Default")
      (node (ref "U13") (pin "5") (pinfunction "A4_5") (pintype "input"))
    )
    (net (code "91") (name "V_HS_PWM") (class "Default")
      (node (ref "U13") (pin "3") (pinfunction "A2_3") (pintype "input"))
    )
    (net (code "92") (name "V_LS_PWM") (class "Default")
      (node (ref "U13") (pin "2") (pinfunction "A1_2") (pintype "input"))
    )
    (net (code "93") (name "W_HS_PWM") (class "Default")
      (node (ref "U13") (pin "9") (pinfunction "A8_9") (pintype "input"))
    )
    (net (code "94") (name "W_LS_PWM") (class "Default")
      (node (ref "U13") (pin "8") (pinfunction "A7_8") (pintype "input"))
    )
    (net (code "95") (name "unconnected-(U13-Y3-Pad16)") (class "Default")
      (node (ref "U13") (pin "16") (pinfunction "Y3_16") (pintype "tri_state"))
    )
    (net (code "96") (name "unconnected-(U13-Y6-Pad13)") (class "Default")
      (node (ref "U13") (pin "13") (pinfunction "Y6_13") (pintype "tri_state"))
    )
  )
)
